# LinuxBoard_v1_7.net
KiCad netlist of a schematic drawn in EAGLE
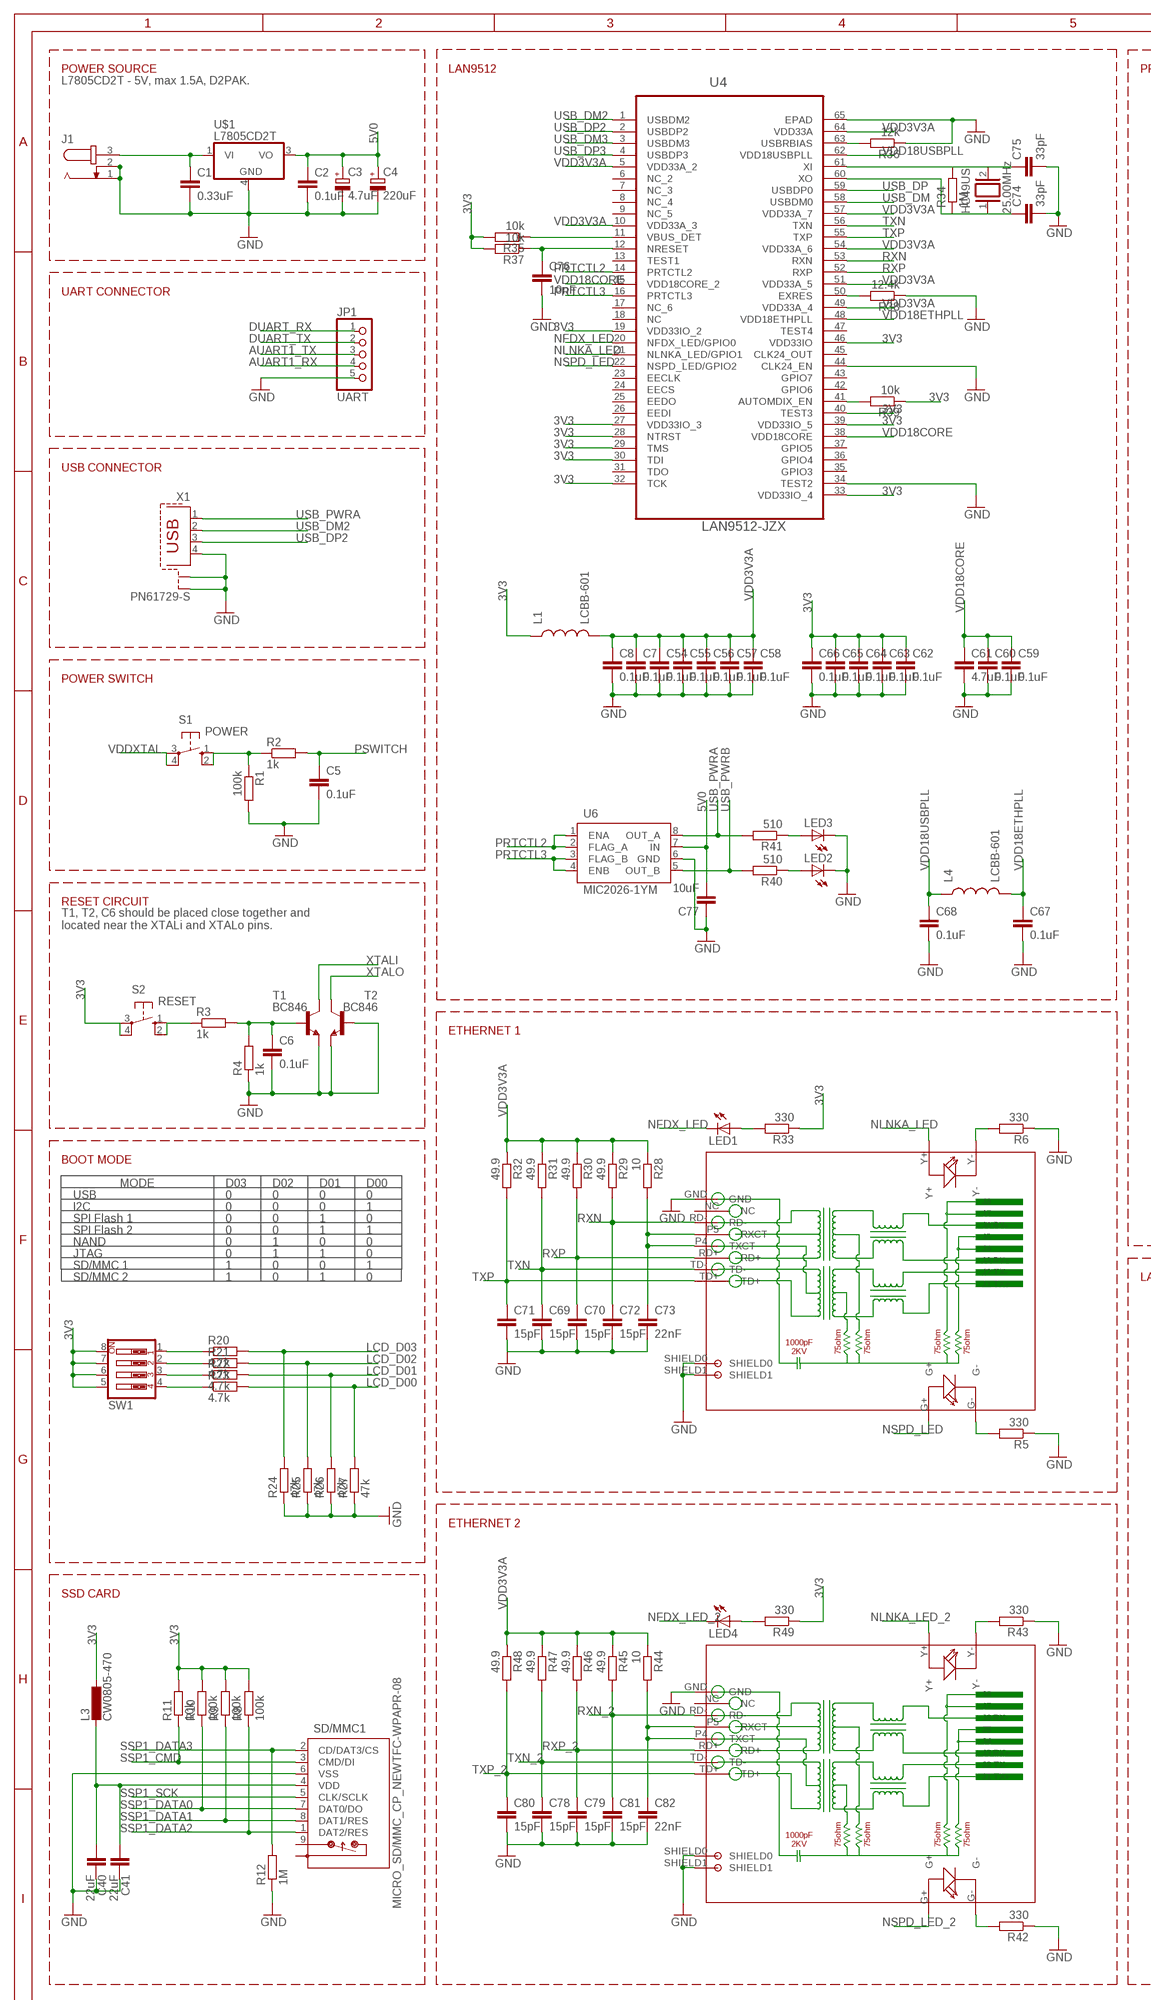
[diagram p0: schematic, sheet 1, part 1 of 2]
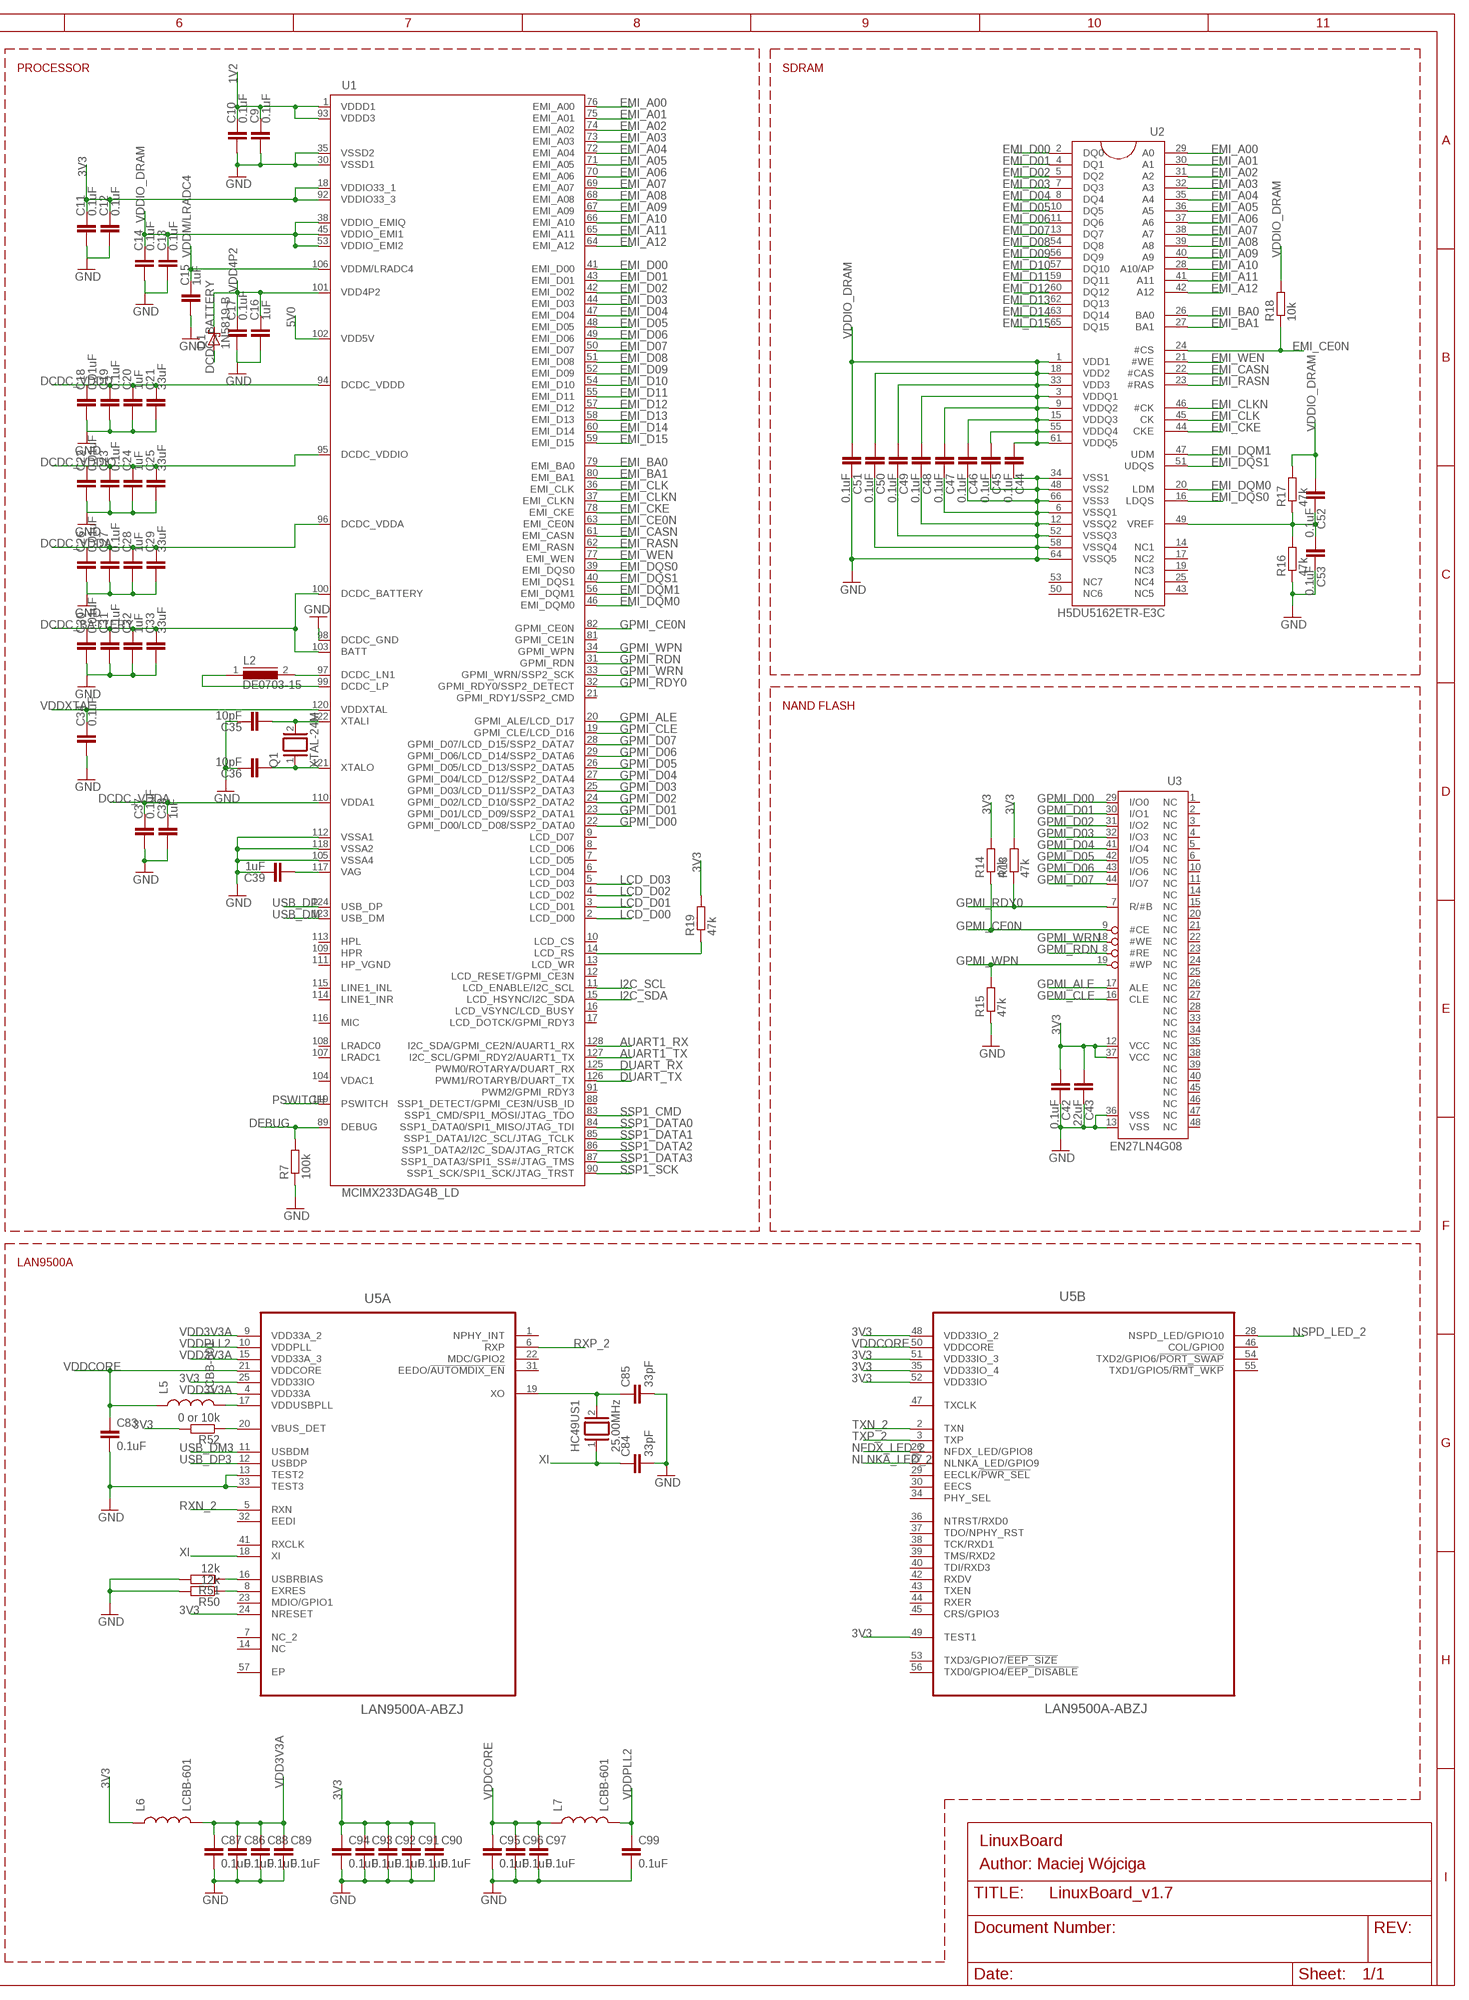
[diagram p1: schematic, sheet 1, part 2 of 2]

(export (version "E")
  (design (tool "Eeschema 10.0.6"))
  (components
    (comp (ref "C1")
      (value "0.33uF")
      (footprint "eagle-import:C0805")
      (libsource (lib "eagle-import") (part "C-EUC0805"))
    )
    (comp (ref "C2")
      (value "0.1uF")
      (footprint "eagle-import:C0805")
      (libsource (lib "eagle-import") (part "C-EUC0805"))
    )
    (comp (ref "C3")
      (value "4.7uF")
      (footprint "eagle-import:E2-5")
      (libsource (lib "eagle-import") (part "CPOL-EUE2-5"))
    )
    (comp (ref "C4")
      (value "220uF")
      (footprint "eagle-import:E2-5")
      (libsource (lib "eagle-import") (part "CPOL-EUE2-5"))
    )
    (comp (ref "C5")
      (value "0.1uF")
      (footprint "eagle-import:C0805")
      (libsource (lib "eagle-import") (part "C-EUC0805"))
    )
    (comp (ref "C6")
      (value "0.1uF")
      (footprint "eagle-import:C0805")
      (libsource (lib "eagle-import") (part "C-EUC0805"))
    )
    (comp (ref "C7")
      (value "0.1uF")
      (footprint "eagle-import:C0805")
      (libsource (lib "eagle-import") (part "C-EUC0805"))
    )
    (comp (ref "C8")
      (value "0.1uF")
      (footprint "eagle-import:C0805")
      (libsource (lib "eagle-import") (part "C-EUC0805"))
    )
    (comp (ref "C9")
      (value "0.1uF")
      (footprint "eagle-import:C0805")
      (libsource (lib "eagle-import") (part "C-EUC0805"))
    )
    (comp (ref "C10")
      (value "0.1uF")
      (footprint "eagle-import:C0805")
      (libsource (lib "eagle-import") (part "C-EUC0805"))
    )
    (comp (ref "C11")
      (value "0.1uF")
      (footprint "eagle-import:C0805")
      (libsource (lib "eagle-import") (part "C-EUC0805"))
    )
    (comp (ref "C12")
      (value "0.1uF")
      (footprint "eagle-import:C0805")
      (libsource (lib "eagle-import") (part "C-EUC0805"))
    )
    (comp (ref "C13")
      (value "0.1uF")
      (footprint "eagle-import:C0805")
      (libsource (lib "eagle-import") (part "C-EUC0805"))
    )
    (comp (ref "C14")
      (value "0.1uF")
      (footprint "eagle-import:C0805")
      (libsource (lib "eagle-import") (part "C-EUC0805"))
    )
    (comp (ref "C15")
      (value "1uF")
      (footprint "eagle-import:C0805")
      (libsource (lib "eagle-import") (part "C-EUC0805"))
    )
    (comp (ref "C16")
      (value "1uF")
      (footprint "eagle-import:C0805")
      (libsource (lib "eagle-import") (part "C-EUC0805"))
    )
    (comp (ref "C17")
      (value "0.1uF")
      (footprint "eagle-import:C0805")
      (libsource (lib "eagle-import") (part "C-EUC0805"))
    )
    (comp (ref "C18")
      (value "0.01uF")
      (footprint "eagle-import:C0805")
      (libsource (lib "eagle-import") (part "C-EUC0805"))
    )
    (comp (ref "C19")
      (value "0.1uF")
      (footprint "eagle-import:C0805")
      (libsource (lib "eagle-import") (part "C-EUC0805"))
    )
    (comp (ref "C20")
      (value "1uF")
      (footprint "eagle-import:C0805")
      (libsource (lib "eagle-import") (part "C-EUC0805"))
    )
    (comp (ref "C21")
      (value "33uF")
      (footprint "eagle-import:C0805")
      (libsource (lib "eagle-import") (part "C-EUC0805"))
    )
    (comp (ref "C22")
      (value "0.01uF")
      (footprint "eagle-import:C0805")
      (libsource (lib "eagle-import") (part "C-EUC0805"))
    )
    (comp (ref "C23")
      (value "0.1uF")
      (footprint "eagle-import:C0805")
      (libsource (lib "eagle-import") (part "C-EUC0805"))
    )
    (comp (ref "C24")
      (value "1uF")
      (footprint "eagle-import:C0805")
      (libsource (lib "eagle-import") (part "C-EUC0805"))
    )
    (comp (ref "C25")
      (value "33uF")
      (footprint "eagle-import:C0805")
      (libsource (lib "eagle-import") (part "C-EUC0805"))
    )
    (comp (ref "C26")
      (value "0.01uF")
      (footprint "eagle-import:C0805")
      (libsource (lib "eagle-import") (part "C-EUC0805"))
    )
    (comp (ref "C27")
      (value "0.1uF")
      (footprint "eagle-import:C0805")
      (libsource (lib "eagle-import") (part "C-EUC0805"))
    )
    (comp (ref "C28")
      (value "1uF")
      (footprint "eagle-import:C0805")
      (libsource (lib "eagle-import") (part "C-EUC0805"))
    )
    (comp (ref "C29")
      (value "33uF")
      (footprint "eagle-import:C0805")
      (libsource (lib "eagle-import") (part "C-EUC0805"))
    )
    (comp (ref "C30")
      (value "0.01uF")
      (footprint "eagle-import:C0805")
      (libsource (lib "eagle-import") (part "C-EUC0805"))
    )
    (comp (ref "C31")
      (value "0.1uF")
      (footprint "eagle-import:C0805")
      (libsource (lib "eagle-import") (part "C-EUC0805"))
    )
    (comp (ref "C32")
      (value "1uF")
      (footprint "eagle-import:C0805")
      (libsource (lib "eagle-import") (part "C-EUC0805"))
    )
    (comp (ref "C33")
      (value "33uF")
      (footprint "eagle-import:C0805")
      (libsource (lib "eagle-import") (part "C-EUC0805"))
    )
    (comp (ref "C34")
      (value "0.1uF")
      (footprint "eagle-import:C0805")
      (libsource (lib "eagle-import") (part "C-EUC0805"))
    )
    (comp (ref "C35")
      (value "10pF")
      (footprint "eagle-import:C0805")
      (libsource (lib "eagle-import") (part "C-EUC0805"))
    )
    (comp (ref "C36")
      (value "10pF")
      (footprint "eagle-import:C0805")
      (libsource (lib "eagle-import") (part "C-EUC0805"))
    )
    (comp (ref "C37")
      (value "0.1uF")
      (footprint "eagle-import:C0805")
      (libsource (lib "eagle-import") (part "C-EUC0805"))
    )
    (comp (ref "C38")
      (value "1uF")
      (footprint "eagle-import:C0805")
      (libsource (lib "eagle-import") (part "C-EUC0805"))
    )
    (comp (ref "C39")
      (value "1uF")
      (footprint "eagle-import:C0805")
      (libsource (lib "eagle-import") (part "C-EUC0805"))
    )
    (comp (ref "C40")
      (value "22uF")
      (footprint "eagle-import:C0805")
      (libsource (lib "eagle-import") (part "C-EUC0805"))
    )
    (comp (ref "C41")
      (value "22uF")
      (footprint "eagle-import:C0805")
      (libsource (lib "eagle-import") (part "C-EUC0805"))
    )
    (comp (ref "C42")
      (value "0.1uF")
      (footprint "eagle-import:C0805")
      (libsource (lib "eagle-import") (part "C-EUC0805"))
    )
    (comp (ref "C43")
      (value "22uF")
      (footprint "eagle-import:C0805")
      (libsource (lib "eagle-import") (part "C-EUC0805"))
    )
    (comp (ref "C44")
      (value "0.1uF")
      (footprint "eagle-import:C0805")
      (libsource (lib "eagle-import") (part "C-EUC0805"))
    )
    (comp (ref "C45")
      (value "0.1uF")
      (footprint "eagle-import:C0805")
      (libsource (lib "eagle-import") (part "C-EUC0805"))
    )
    (comp (ref "C46")
      (value "0.1uF")
      (footprint "eagle-import:C0805")
      (libsource (lib "eagle-import") (part "C-EUC0805"))
    )
    (comp (ref "C47")
      (value "0.1uF")
      (footprint "eagle-import:C0805")
      (libsource (lib "eagle-import") (part "C-EUC0805"))
    )
    (comp (ref "C48")
      (value "0.1uF")
      (footprint "eagle-import:C0805")
      (libsource (lib "eagle-import") (part "C-EUC0805"))
    )
    (comp (ref "C49")
      (value "0.1uF")
      (footprint "eagle-import:C0805")
      (libsource (lib "eagle-import") (part "C-EUC0805"))
    )
    (comp (ref "C50")
      (value "0.1uF")
      (footprint "eagle-import:C0805")
      (libsource (lib "eagle-import") (part "C-EUC0805"))
    )
    (comp (ref "C51")
      (value "0.1uF")
      (footprint "eagle-import:C0805")
      (libsource (lib "eagle-import") (part "C-EUC0805"))
    )
    (comp (ref "C52")
      (value "0.1uF")
      (footprint "eagle-import:C0805")
      (libsource (lib "eagle-import") (part "C-EUC0805"))
    )
    (comp (ref "C53")
      (value "0.1uF")
      (footprint "eagle-import:C0805")
      (libsource (lib "eagle-import") (part "C-EUC0805"))
    )
    (comp (ref "C54")
      (value "0.1uF")
      (footprint "eagle-import:C0805")
      (libsource (lib "eagle-import") (part "C-EUC0805"))
    )
    (comp (ref "C55")
      (value "0.1uF")
      (footprint "eagle-import:C0805")
      (libsource (lib "eagle-import") (part "C-EUC0805"))
    )
    (comp (ref "C56")
      (value "0.1uF")
      (footprint "eagle-import:C0805")
      (libsource (lib "eagle-import") (part "C-EUC0805"))
    )
    (comp (ref "C57")
      (value "0.1uF")
      (footprint "eagle-import:C0805")
      (libsource (lib "eagle-import") (part "C-EUC0805"))
    )
    (comp (ref "C58")
      (value "0.1uF")
      (footprint "eagle-import:C0805")
      (libsource (lib "eagle-import") (part "C-EUC0805"))
    )
    (comp (ref "C59")
      (value "0.1uF")
      (footprint "eagle-import:C0805")
      (libsource (lib "eagle-import") (part "C-EUC0805"))
    )
    (comp (ref "C60")
      (value "0.1uF")
      (footprint "eagle-import:C0805")
      (libsource (lib "eagle-import") (part "C-EUC0805"))
    )
    (comp (ref "C61")
      (value "4.7uF")
      (footprint "eagle-import:C0805")
      (libsource (lib "eagle-import") (part "C-EUC0805"))
    )
    (comp (ref "C62")
      (value "0.1uF")
      (footprint "eagle-import:C0805")
      (libsource (lib "eagle-import") (part "C-EUC0805"))
    )
    (comp (ref "C63")
      (value "0.1uF")
      (footprint "eagle-import:C0805")
      (libsource (lib "eagle-import") (part "C-EUC0805"))
    )
    (comp (ref "C64")
      (value "0.1uF")
      (footprint "eagle-import:C0805")
      (libsource (lib "eagle-import") (part "C-EUC0805"))
    )
    (comp (ref "C65")
      (value "0.1uF")
      (footprint "eagle-import:C0805")
      (libsource (lib "eagle-import") (part "C-EUC0805"))
    )
    (comp (ref "C66")
      (value "0.1uF")
      (footprint "eagle-import:C0805")
      (libsource (lib "eagle-import") (part "C-EUC0805"))
    )
    (comp (ref "C67")
      (value "0.1uF")
      (footprint "eagle-import:C0805")
      (libsource (lib "eagle-import") (part "C-EUC0805"))
    )
    (comp (ref "C68")
      (value "0.1uF")
      (footprint "eagle-import:C0805")
      (libsource (lib "eagle-import") (part "C-EUC0805"))
    )
    (comp (ref "C69")
      (value "15pF")
      (footprint "eagle-import:C0805")
      (libsource (lib "eagle-import") (part "C-EUC0805"))
    )
    (comp (ref "C70")
      (value "15pF")
      (footprint "eagle-import:C0805")
      (libsource (lib "eagle-import") (part "C-EUC0805"))
    )
    (comp (ref "C71")
      (value "15pF")
      (footprint "eagle-import:C0805")
      (libsource (lib "eagle-import") (part "C-EUC0805"))
    )
    (comp (ref "C72")
      (value "15pF")
      (footprint "eagle-import:C0805")
      (libsource (lib "eagle-import") (part "C-EUC0805"))
    )
    (comp (ref "C73")
      (value "22nF")
      (footprint "eagle-import:C0805")
      (libsource (lib "eagle-import") (part "C-EUC0805"))
    )
    (comp (ref "C74")
      (value "33pF")
      (footprint "eagle-import:C0805")
      (libsource (lib "eagle-import") (part "C-EUC0805"))
    )
    (comp (ref "C75")
      (value "33pF")
      (footprint "eagle-import:C0805")
      (libsource (lib "eagle-import") (part "C-EUC0805"))
    )
    (comp (ref "C76")
      (value "10nF")
      (footprint "eagle-import:C0805")
      (libsource (lib "eagle-import") (part "C-EUC0805"))
    )
    (comp (ref "C77")
      (value "10uF")
      (footprint "eagle-import:C0805")
      (libsource (lib "eagle-import") (part "C-EUC0805"))
    )
    (comp (ref "C78")
      (value "15pF")
      (footprint "eagle-import:C0805")
      (libsource (lib "eagle-import") (part "C-EUC0805"))
    )
    (comp (ref "C79")
      (value "15pF")
      (footprint "eagle-import:C0805")
      (libsource (lib "eagle-import") (part "C-EUC0805"))
    )
    (comp (ref "C80")
      (value "15pF")
      (footprint "eagle-import:C0805")
      (libsource (lib "eagle-import") (part "C-EUC0805"))
    )
    (comp (ref "C81")
      (value "15pF")
      (footprint "eagle-import:C0805")
      (libsource (lib "eagle-import") (part "C-EUC0805"))
    )
    (comp (ref "C82")
      (value "22nF")
      (footprint "eagle-import:C0805")
      (libsource (lib "eagle-import") (part "C-EUC0805"))
    )
    (comp (ref "C83")
      (value "0.1uF")
      (footprint "eagle-import:C0805")
      (libsource (lib "eagle-import") (part "C-EUC0805"))
    )
    (comp (ref "C84")
      (value "33pF")
      (footprint "eagle-import:C0805")
      (libsource (lib "eagle-import") (part "C-EUC0805"))
    )
    (comp (ref "C85")
      (value "33pF")
      (footprint "eagle-import:C0805")
      (libsource (lib "eagle-import") (part "C-EUC0805"))
    )
    (comp (ref "C86")
      (value "0.1uF")
      (footprint "eagle-import:C0805")
      (libsource (lib "eagle-import") (part "C-EUC0805"))
    )
    (comp (ref "C87")
      (value "0.1uF")
      (footprint "eagle-import:C0805")
      (libsource (lib "eagle-import") (part "C-EUC0805"))
    )
    (comp (ref "C88")
      (value "0.1uF")
      (footprint "eagle-import:C0805")
      (libsource (lib "eagle-import") (part "C-EUC0805"))
    )
    (comp (ref "C89")
      (value "0.1uF")
      (footprint "eagle-import:C0805")
      (libsource (lib "eagle-import") (part "C-EUC0805"))
    )
    (comp (ref "C90")
      (value "0.1uF")
      (footprint "eagle-import:C0805")
      (libsource (lib "eagle-import") (part "C-EUC0805"))
    )
    (comp (ref "C91")
      (value "0.1uF")
      (footprint "eagle-import:C0805")
      (libsource (lib "eagle-import") (part "C-EUC0805"))
    )
    (comp (ref "C92")
      (value "0.1uF")
      (footprint "eagle-import:C0805")
      (libsource (lib "eagle-import") (part "C-EUC0805"))
    )
    (comp (ref "C93")
      (value "0.1uF")
      (footprint "eagle-import:C0805")
      (libsource (lib "eagle-import") (part "C-EUC0805"))
    )
    (comp (ref "C94")
      (value "0.1uF")
      (footprint "eagle-import:C0805")
      (libsource (lib "eagle-import") (part "C-EUC0805"))
    )
    (comp (ref "C95")
      (value "0.1uF")
      (footprint "eagle-import:C0805")
      (libsource (lib "eagle-import") (part "C-EUC0805"))
    )
    (comp (ref "C96")
      (value "0.1uF")
      (footprint "eagle-import:C0805")
      (libsource (lib "eagle-import") (part "C-EUC0805"))
    )
    (comp (ref "C97")
      (value "0.1uF")
      (footprint "eagle-import:C0805")
      (libsource (lib "eagle-import") (part "C-EUC0805"))
    )
    (comp (ref "C99")
      (value "0.1uF")
      (footprint "eagle-import:C0805")
      (libsource (lib "eagle-import") (part "C-EUC0805"))
    )
    (comp (ref "D1")
      (value "1N5819-B")
      (footprint "eagle-import:DO41-7.6")
      (libsource (lib "eagle-import") (part "1N5819-B"))
    )
    (comp (ref "HC49US")
      (value "25.00MHz")
      (footprint "eagle-import:QS")
      (libsource (lib "eagle-import") (part "XTAL/S"))
    )
    (comp (ref "HC49US1")
      (value "25.00MHz")
      (footprint "eagle-import:QS")
      (libsource (lib "eagle-import") (part "XTAL/S"))
    )
    (comp (ref "J1")
      (value "JACK-PLUG0")
      (footprint "eagle-import:SPC4077")
      (libsource (lib "eagle-import") (part "JACK-PLUG0"))
    )
    (comp (ref "JP1")
      (value "UART")
      (footprint "eagle-import:1X05")
      (libsource (lib "eagle-import") (part "PINHD-1X5"))
    )
    (comp (ref "L1")
      (value "LCBB-601")
      (footprint "eagle-import:0805")
      (libsource (lib "eagle-import") (part "INDUCTOR0805"))
    )
    (comp (ref "L2")
      (value "DE0703-15")
      (footprint "eagle-import:DR73")
      (libsource (lib "eagle-import") (part "DR73"))
    )
    (comp (ref "L3")
      (value "CW0805-470")
      (footprint "eagle-import:L2012C")
      (libsource (lib "eagle-import") (part "L-EUL2012C"))
    )
    (comp (ref "L4")
      (value "LCBB-601")
      (footprint "eagle-import:0805")
      (libsource (lib "eagle-import") (part "INDUCTOR0805"))
    )
    (comp (ref "L5")
      (value "LCBB-601")
      (footprint "eagle-import:0805")
      (libsource (lib "eagle-import") (part "INDUCTOR0805"))
    )
    (comp (ref "L6")
      (value "LCBB-601")
      (footprint "eagle-import:0805")
      (libsource (lib "eagle-import") (part "INDUCTOR0805"))
    )
    (comp (ref "L7")
      (value "LCBB-601")
      (footprint "eagle-import:0805")
      (libsource (lib "eagle-import") (part "INDUCTOR0805"))
    )
    (comp (ref "LED1")
      (value "LEDSML0805")
      (footprint "eagle-import:SML0805")
      (libsource (lib "eagle-import") (part "LEDSML0805"))
    )
    (comp (ref "LED2")
      (value "LEDSML0805")
      (footprint "eagle-import:SML0805")
      (libsource (lib "eagle-import") (part "LEDSML0805"))
    )
    (comp (ref "LED3")
      (value "LEDSML0805")
      (footprint "eagle-import:SML0805")
      (libsource (lib "eagle-import") (part "LEDSML0805"))
    )
    (comp (ref "LED4")
      (value "LEDSML0805")
      (footprint "eagle-import:SML0805")
      (libsource (lib "eagle-import") (part "LEDSML0805"))
    )
    (comp (ref "Q1")
      (value "XTAL-24M")
      (footprint "eagle-import:QS")
      (libsource (lib "eagle-import") (part "XTAL/S"))
    )
    (comp (ref "R1")
      (value "100k")
      (footprint "eagle-import:R0805")
      (libsource (lib "eagle-import") (part "R-EU_R0805"))
    )
    (comp (ref "R2")
      (value "1k")
      (footprint "eagle-import:R0805")
      (libsource (lib "eagle-import") (part "R-EU_R0805"))
    )
    (comp (ref "R3")
      (value "1k")
      (footprint "eagle-import:R0805")
      (libsource (lib "eagle-import") (part "R-EU_R0805"))
    )
    (comp (ref "R4")
      (value "1k")
      (footprint "eagle-import:R0805")
      (libsource (lib "eagle-import") (part "R-EU_R0805"))
    )
    (comp (ref "R5")
      (value "330")
      (footprint "eagle-import:R0805")
      (libsource (lib "eagle-import") (part "R-EU_R0805"))
    )
    (comp (ref "R6")
      (value "330")
      (footprint "eagle-import:R0805")
      (libsource (lib "eagle-import") (part "R-EU_R0805"))
    )
    (comp (ref "R7")
      (value "100k")
      (footprint "eagle-import:R0805")
      (libsource (lib "eagle-import") (part "R-EU_R0805"))
    )
    (comp (ref "R8")
      (value "100k")
      (footprint "eagle-import:R0805")
      (libsource (lib "eagle-import") (part "R-EU_R0805"))
    )
    (comp (ref "R9")
      (value "100k")
      (footprint "eagle-import:R0805")
      (libsource (lib "eagle-import") (part "R-EU_R0805"))
    )
    (comp (ref "R10")
      (value "100k")
      (footprint "eagle-import:R0805")
      (libsource (lib "eagle-import") (part "R-EU_R0805"))
    )
    (comp (ref "R11")
      (value "10k")
      (footprint "eagle-import:R0805")
      (libsource (lib "eagle-import") (part "R-EU_R0805"))
    )
    (comp (ref "R12")
      (value "1M")
      (footprint "eagle-import:R0805")
      (libsource (lib "eagle-import") (part "R-EU_R0805"))
    )
    (comp (ref "R13")
      (value "47k")
      (footprint "eagle-import:R0805")
      (libsource (lib "eagle-import") (part "R-EU_R0805"))
    )
    (comp (ref "R14")
      (value "47k")
      (footprint "eagle-import:R0805")
      (libsource (lib "eagle-import") (part "R-EU_R0805"))
    )
    (comp (ref "R15")
      (value "47k")
      (footprint "eagle-import:R0805")
      (libsource (lib "eagle-import") (part "R-EU_R0805"))
    )
    (comp (ref "R16")
      (value "47k")
      (footprint "eagle-import:R0805")
      (libsource (lib "eagle-import") (part "R-EU_R0805"))
    )
    (comp (ref "R17")
      (value "47k")
      (footprint "eagle-import:R0805")
      (libsource (lib "eagle-import") (part "R-EU_R0805"))
    )
    (comp (ref "R18")
      (value "10k")
      (footprint "eagle-import:R0805")
      (libsource (lib "eagle-import") (part "R-EU_R0805"))
    )
    (comp (ref "R19")
      (value "47k")
      (footprint "eagle-import:R0805")
      (libsource (lib "eagle-import") (part "R-EU_R0805"))
    )
    (comp (ref "R20")
      (value "4.7k")
      (footprint "eagle-import:R0805")
      (libsource (lib "eagle-import") (part "R-EU_R0805"))
    )
    (comp (ref "R21")
      (value "4.7k")
      (footprint "eagle-import:R0805")
      (libsource (lib "eagle-import") (part "R-EU_R0805"))
    )
    (comp (ref "R22")
      (value "4.7k")
      (footprint "eagle-import:R0805")
      (libsource (lib "eagle-import") (part "R-EU_R0805"))
    )
    (comp (ref "R23")
      (value "4.7k")
      (footprint "eagle-import:R0805")
      (libsource (lib "eagle-import") (part "R-EU_R0805"))
    )
    (comp (ref "R24")
      (value "47k")
      (footprint "eagle-import:R0805")
      (libsource (lib "eagle-import") (part "R-EU_R0805"))
    )
    (comp (ref "R25")
      (value "47k")
      (footprint "eagle-import:R0805")
      (libsource (lib "eagle-import") (part "R-EU_R0805"))
    )
    (comp (ref "R26")
      (value "47k")
      (footprint "eagle-import:R0805")
      (libsource (lib "eagle-import") (part "R-EU_R0805"))
    )
    (comp (ref "R27")
      (value "47k")
      (footprint "eagle-import:R0805")
      (libsource (lib "eagle-import") (part "R-EU_R0805"))
    )
    (comp (ref "R28")
      (value "10")
      (footprint "eagle-import:R0805")
      (libsource (lib "eagle-import") (part "R-EU_R0805"))
    )
    (comp (ref "R29")
      (value "49.9")
      (footprint "eagle-import:R0805")
      (libsource (lib "eagle-import") (part "R-EU_R0805"))
    )
    (comp (ref "R30")
      (value "49.9")
      (footprint "eagle-import:R0805")
      (libsource (lib "eagle-import") (part "R-EU_R0805"))
    )
    (comp (ref "R31")
      (value "49.9")
      (footprint "eagle-import:R0805")
      (libsource (lib "eagle-import") (part "R-EU_R0805"))
    )
    (comp (ref "R32")
      (value "49.9")
      (footprint "eagle-import:R0805")
      (libsource (lib "eagle-import") (part "R-EU_R0805"))
    )
    (comp (ref "R33")
      (value "330")
      (footprint "eagle-import:R0805")
      (libsource (lib "eagle-import") (part "R-EU_R0805"))
    )
    (comp (ref "R34")
      (value "1M")
      (footprint "eagle-import:R0805")
      (libsource (lib "eagle-import") (part "R-EU_R0805"))
    )
    (comp (ref "R35")
      (value "10k")
      (footprint "eagle-import:R0805")
      (libsource (lib "eagle-import") (part "R-EU_R0805"))
    )
    (comp (ref "R36")
      (value "12k")
      (footprint "eagle-import:R0805")
      (libsource (lib "eagle-import") (part "R-EU_R0805"))
    )
    (comp (ref "R37")
      (value "10k")
      (footprint "eagle-import:R0805")
      (libsource (lib "eagle-import") (part "R-EU_R0805"))
    )
    (comp (ref "R38")
      (value "12.4k")
      (footprint "eagle-import:R0805")
      (libsource (lib "eagle-import") (part "R-EU_R0805"))
    )
    (comp (ref "R39")
      (value "10k")
      (footprint "eagle-import:R0805")
      (libsource (lib "eagle-import") (part "R-EU_R0805"))
    )
    (comp (ref "R40")
      (value "510")
      (footprint "eagle-import:R0805")
      (libsource (lib "eagle-import") (part "R-EU_R0805"))
    )
    (comp (ref "R41")
      (value "510")
      (footprint "eagle-import:R0805")
      (libsource (lib "eagle-import") (part "R-EU_R0805"))
    )
    (comp (ref "R42")
      (value "330")
      (footprint "eagle-import:R0805")
      (libsource (lib "eagle-import") (part "R-EU_R0805"))
    )
    (comp (ref "R43")
      (value "330")
      (footprint "eagle-import:R0805")
      (libsource (lib "eagle-import") (part "R-EU_R0805"))
    )
    (comp (ref "R44")
      (value "10")
      (footprint "eagle-import:R0805")
      (libsource (lib "eagle-import") (part "R-EU_R0805"))
    )
    (comp (ref "R45")
      (value "49.9")
      (footprint "eagle-import:R0805")
      (libsource (lib "eagle-import") (part "R-EU_R0805"))
    )
    (comp (ref "R46")
      (value "49.9")
      (footprint "eagle-import:R0805")
      (libsource (lib "eagle-import") (part "R-EU_R0805"))
    )
    (comp (ref "R47")
      (value "49.9")
      (footprint "eagle-import:R0805")
      (libsource (lib "eagle-import") (part "R-EU_R0805"))
    )
    (comp (ref "R48")
      (value "49.9")
      (footprint "eagle-import:R0805")
      (libsource (lib "eagle-import") (part "R-EU_R0805"))
    )
    (comp (ref "R49")
      (value "330")
      (footprint "eagle-import:R0805")
      (libsource (lib "eagle-import") (part "R-EU_R0805"))
    )
    (comp (ref "R50")
      (value "12k")
      (footprint "eagle-import:R0805")
      (libsource (lib "eagle-import") (part "R-EU_R0805"))
    )
    (comp (ref "R51")
      (value "12k")
      (footprint "eagle-import:R0805")
      (libsource (lib "eagle-import") (part "R-EU_R0805"))
    )
    (comp (ref "R52")
      (value "0 or 10k")
      (footprint "eagle-import:R0805")
      (libsource (lib "eagle-import") (part "R-EU_R0805"))
    )
    (comp (ref "RJ1")
      (value "HR911105A")
      (footprint "eagle-import:HR911105A")
      (libsource (lib "eagle-import") (part "HR911105A"))
    )
    (comp (ref "RJ2")
      (value "HR911105A")
      (footprint "eagle-import:HR911105A")
      (libsource (lib "eagle-import") (part "HR911105A"))
    )
    (comp (ref "S1")
      (value "POWER")
      (footprint "eagle-import:B3F-10XX")
      (fields (field (name "MPN") "B3F-1000"))
      (libsource (lib "eagle-import") (part "10-XX"))
    )
    (comp (ref "S2")
      (value "RESET")
      (footprint "eagle-import:B3F-10XX")
      (fields (field (name "MPN") "B3F-1000"))
      (libsource (lib "eagle-import") (part "10-XX"))
    )
    (comp (ref "SD/MMC1")
      (value "MICRO_SD/MMC_CP_NEWTFC-WPAPR-08")
      (footprint "eagle-import:TFC-WPAPR-08")
      (libsource (lib "eagle-import") (part "MICRO_SD/MMC_CP_NEWTFC-WPAPR-08"))
    )
    (comp (ref "SW1")
      (value "SW_DIP-4")
      (footprint "eagle-import:EDG-04")
      (libsource (lib "eagle-import") (part "SW_DIP-4"))
    )
    (comp (ref "T1")
      (value "BC846")
      (footprint "eagle-import:SOT23")
      (libsource (lib "eagle-import") (part "BC846"))
    )
    (comp (ref "T2")
      (value "BC846")
      (footprint "eagle-import:SOT23")
      (libsource (lib "eagle-import") (part "BC846"))
    )
    (comp (ref "U$1")
      (value "L7805CD2T")
      (footprint "eagle-import:D2PAK-3")
      (libsource (lib "eagle-import") (part "L7805CD2T"))
    )
    (comp (ref "U1")
      (value "MCIMX233DAG4B_LD")
      (footprint "eagle-import:TQFP128LD")
      (libsource (lib "eagle-import") (part "MCIMX233DAG4B_LD"))
    )
    (comp (ref "U2")
      (value "H5DU5162ETR-E3C")
      (footprint "eagle-import:66TSOP-II")
      (libsource (lib "eagle-import") (part "HY5DU121622D(L)T(P)-J"))
    )
    (comp (ref "U3")
      (value "EN27LN4G08")
      (footprint "eagle-import:TSOP48")
      (libsource (lib "eagle-import") (part "H27UBG8T2A"))
    )
    (comp (ref "U4")
      (value "LAN9512-JZX")
      (footprint "eagle-import:QFN50P900X900X100-65N")
      (libsource (lib "eagle-import") (part "LAN9512-JZX"))
    )
    (comp (ref "U5")
      (value "LAN9500A-ABZJ")
      (footprint "eagle-import:QFN50P800X800X100-57N")
      (libsource (lib "eagle-import") (part "LAN9500A-ABZJ"))
    )
    (comp (ref "U6")
      (value "MIC2026-1YM")
      (footprint "eagle-import:SO-8")
      (libsource (lib "eagle-import") (part "MIC2026-1YM"))
    )
    (comp (ref "X1")
      (value "PN61729-S")
      (footprint "eagle-import:PN61729-S")
      (libsource (lib "eagle-import") (part "PN61729-S"))
    )
  )
  (nets
    (net (code "1") (name "/1V2") (class "Default")
      (node (ref "C10") (pin "1") (pinfunction "1_1") (pintype "passive"))
      (node (ref "C9") (pin "1") (pinfunction "1_1") (pintype "passive"))
      (node (ref "U1") (pin "1") (pinfunction "VDDD1_1") (pintype "power_in"))
      (node (ref "U1") (pin "93") (pinfunction "VDDD3_93") (pintype "power_in"))
    )
    (net (code "2") (name "/3V3") (class "Default")
      (node (ref "C11") (pin "1") (pinfunction "1_1") (pintype "passive"))
      (node (ref "C12") (pin "1") (pinfunction "1_1") (pintype "passive"))
      (node (ref "C42") (pin "2") (pinfunction "2_2") (pintype "passive"))
      (node (ref "C43") (pin "2") (pinfunction "2_2") (pintype "passive"))
      (node (ref "C62") (pin "1") (pinfunction "1_1") (pintype "passive"))
      (node (ref "C63") (pin "1") (pinfunction "1_1") (pintype "passive"))
      (node (ref "C64") (pin "1") (pinfunction "1_1") (pintype "passive"))
      (node (ref "C65") (pin "1") (pinfunction "1_1") (pintype "passive"))
      (node (ref "C66") (pin "1") (pinfunction "1_1") (pintype "passive"))
      (node (ref "C90") (pin "1") (pinfunction "1_1") (pintype "passive"))
      (node (ref "C91") (pin "1") (pinfunction "1_1") (pintype "passive"))
      (node (ref "C92") (pin "1") (pinfunction "1_1") (pintype "passive"))
      (node (ref "C93") (pin "1") (pinfunction "1_1") (pintype "passive"))
      (node (ref "C94") (pin "1") (pinfunction "1_1") (pintype "passive"))
      (node (ref "L1") (pin "1") (pinfunction "1_1") (pintype "passive"))
      (node (ref "L3") (pin "1") (pinfunction "1_1") (pintype "passive"))
      (node (ref "L6") (pin "1") (pinfunction "1_1") (pintype "passive"))
      (node (ref "R10") (pin "2") (pinfunction "2_2") (pintype "passive"))
      (node (ref "R11") (pin "2") (pinfunction "2_2") (pintype "passive"))
      (node (ref "R13") (pin "2") (pinfunction "2_2") (pintype "passive"))
      (node (ref "R14") (pin "2") (pinfunction "2_2") (pintype "passive"))
      (node (ref "R19") (pin "2") (pinfunction "2_2") (pintype "passive"))
      (node (ref "R33") (pin "1") (pinfunction "1_1") (pintype "passive"))
      (node (ref "R35") (pin "2") (pinfunction "2_2") (pintype "passive"))
      (node (ref "R37") (pin "2") (pinfunction "2_2") (pintype "passive"))
      (node (ref "R39") (pin "1") (pinfunction "1_1") (pintype "passive"))
      (node (ref "R49") (pin "1") (pinfunction "1_1") (pintype "passive"))
      (node (ref "R52") (pin "2") (pinfunction "2_2") (pintype "passive"))
      (node (ref "R8") (pin "2") (pinfunction "2_2") (pintype "passive"))
      (node (ref "R9") (pin "2") (pinfunction "2_2") (pintype "passive"))
      (node (ref "S2") (pin "3") (pinfunction "P_3") (pintype "passive"))
      (node (ref "S2") (pin "4") (pinfunction "P1_4") (pintype "passive"))
      (node (ref "SW1") (pin "5") (pinfunction "5_5") (pintype "passive"))
      (node (ref "SW1") (pin "6") (pinfunction "6_6") (pintype "passive"))
      (node (ref "SW1") (pin "7") (pinfunction "7_7") (pintype "passive"))
      (node (ref "SW1") (pin "8") (pinfunction "8_8") (pintype "passive"))
      (node (ref "U1") (pin "18") (pinfunction "VDDIO33_1_18") (pintype "power_in"))
      (node (ref "U1") (pin "92") (pinfunction "VDDIO33_3_92") (pintype "power_in"))
      (node (ref "U3") (pin "12") (pinfunction "VCC_12") (pintype "power_in"))
      (node (ref "U3") (pin "37") (pinfunction "VCC_37") (pintype "power_in"))
      (node (ref "U4") (pin "19") (pinfunction "VDD33IO_2_19") (pintype "power_in"))
      (node (ref "U4") (pin "27") (pinfunction "VDD33IO_3_27") (pintype "power_in"))
      (node (ref "U4") (pin "28") (pinfunction "NTRST_28") (pintype "passive"))
      (node (ref "U4") (pin "29") (pinfunction "TMS_29") (pintype "passive"))
      (node (ref "U4") (pin "30") (pinfunction "TDI_30") (pintype "passive"))
      (node (ref "U4") (pin "32") (pinfunction "TCK_32") (pintype "passive"))
      (node (ref "U4") (pin "33") (pinfunction "VDD33IO_4_33") (pintype "power_in"))
      (node (ref "U4") (pin "39") (pinfunction "VDD33IO_5_39") (pintype "power_in"))
      (node (ref "U4") (pin "40") (pinfunction "TEST3_40") (pintype "passive"))
      (node (ref "U4") (pin "46") (pinfunction "VDD33IO_46") (pintype "power_in"))
      (node (ref "U5") (pin "24") (pinfunction "NRESET_24") (pintype "input"))
      (node (ref "U5") (pin "25") (pinfunction "VDD33IO_25") (pintype "power_in"))
      (node (ref "U5") (pin "35") (pinfunction "VDD33IO_4_35") (pintype "power_in"))
      (node (ref "U5") (pin "48") (pinfunction "VDD33IO_2_48") (pintype "power_in"))
      (node (ref "U5") (pin "49") (pinfunction "TEST1_49") (pintype "power_in"))
      (node (ref "U5") (pin "51") (pinfunction "VDD33IO_3_51") (pintype "power_in"))
      (node (ref "U5") (pin "52") (pinfunction "VDD33IO_52") (pintype "power_in"))
    )
    (net (code "3") (name "/5V0") (class "Default")
      (node (ref "C2") (pin "1") (pinfunction "1_1") (pintype "passive"))
      (node (ref "C3") (pin "+") (pinfunction "+_+") (pintype "passive"))
      (node (ref "C4") (pin "+") (pinfunction "+_+") (pintype "passive"))
      (node (ref "C77") (pin "2") (pinfunction "2_2") (pintype "passive"))
      (node (ref "U$1") (pin "3") (pinfunction "VO_3") (pintype "passive"))
      (node (ref "U1") (pin "102") (pinfunction "VDD5V_102") (pintype "power_in"))
      (node (ref "U6") (pin "7") (pinfunction "IN_7") (pintype "input"))
    )
    (net (code "4") (name "/AUART1_RX") (class "Default")
      (node (ref "JP1") (pin "4") (pinfunction "4_4") (pintype "passive"))
      (node (ref "U1") (pin "128") (pinfunction "I2C_SDA/GPMI_CE2N/AUART1_RX_128") (pintype "bidirectional"))
    )
    (net (code "5") (name "/AUART1_TX") (class "Default")
      (node (ref "JP1") (pin "3") (pinfunction "3_3") (pintype "passive"))
      (node (ref "U1") (pin "127") (pinfunction "I2C_SCL/GPMI_RDY2/AUART1_TX_127") (pintype "bidirectional"))
    )
    (net (code "6") (name "/DCDC_BATTERY") (class "Default")
      (node (ref "C30") (pin "1") (pinfunction "1_1") (pintype "passive"))
      (node (ref "C31") (pin "1") (pinfunction "1_1") (pintype "passive"))
      (node (ref "C32") (pin "1") (pinfunction "1_1") (pintype "passive"))
      (node (ref "C33") (pin "1") (pinfunction "1_1") (pintype "passive"))
      (node (ref "D1") (pin "A") (pinfunction "A_A") (pintype "passive"))
      (node (ref "U1") (pin "100") (pinfunction "DCDC_BATTERY_100") (pintype "power_in"))
      (node (ref "U1") (pin "103") (pinfunction "BATT_103") (pintype "input"))
    )
    (net (code "7") (name "/DCDC_VDDA") (class "Default")
      (node (ref "C26") (pin "1") (pinfunction "1_1") (pintype "passive"))
      (node (ref "C27") (pin "1") (pinfunction "1_1") (pintype "passive"))
      (node (ref "C28") (pin "1") (pinfunction "1_1") (pintype "passive"))
      (node (ref "C29") (pin "1") (pinfunction "1_1") (pintype "passive"))
      (node (ref "C37") (pin "1") (pinfunction "1_1") (pintype "passive"))
      (node (ref "C38") (pin "1") (pinfunction "1_1") (pintype "passive"))
      (node (ref "U1") (pin "110") (pinfunction "VDDA1_110") (pintype "power_in"))
      (node (ref "U1") (pin "96") (pinfunction "DCDC_VDDA_96") (pintype "power_in"))
    )
    (net (code "8") (name "/DCDC_VDDD") (class "Default")
      (node (ref "C18") (pin "1") (pinfunction "1_1") (pintype "passive"))
      (node (ref "C19") (pin "1") (pinfunction "1_1") (pintype "passive"))
      (node (ref "C20") (pin "1") (pinfunction "1_1") (pintype "passive"))
      (node (ref "C21") (pin "1") (pinfunction "1_1") (pintype "passive"))
      (node (ref "U1") (pin "94") (pinfunction "DCDC_VDDD_94") (pintype "power_in"))
    )
    (net (code "9") (name "/DCDC_VDDIO") (class "Default")
      (node (ref "C22") (pin "1") (pinfunction "1_1") (pintype "passive"))
      (node (ref "C23") (pin "1") (pinfunction "1_1") (pintype "passive"))
      (node (ref "C24") (pin "1") (pinfunction "1_1") (pintype "passive"))
      (node (ref "C25") (pin "1") (pinfunction "1_1") (pintype "passive"))
      (node (ref "U1") (pin "95") (pinfunction "DCDC_VDDIO_95") (pintype "power_in"))
    )
    (net (code "10") (name "/DEBUG") (class "Default")
      (node (ref "R7") (pin "2") (pinfunction "2_2") (pintype "passive"))
      (node (ref "U1") (pin "89") (pinfunction "DEBUG_89") (pintype "bidirectional"))
    )
    (net (code "11") (name "/DUART_RX") (class "Default")
      (node (ref "JP1") (pin "1") (pinfunction "1_1") (pintype "passive"))
      (node (ref "U1") (pin "125") (pinfunction "PWM0/ROTARYA/DUART_RX_125") (pintype "bidirectional"))
    )
    (net (code "12") (name "/DUART_TX") (class "Default")
      (node (ref "JP1") (pin "2") (pinfunction "2_2") (pintype "passive"))
      (node (ref "U1") (pin "126") (pinfunction "PWM1/ROTARYB/DUART_TX_126") (pintype "bidirectional"))
    )
    (net (code "13") (name "/EMI_A00") (class "Default")
      (node (ref "U1") (pin "76") (pinfunction "EMI_A00_76") (pintype "bidirectional"))
      (node (ref "U2") (pin "29") (pinfunction "A0_29") (pintype "input"))
    )
    (net (code "14") (name "/EMI_A01") (class "Default")
      (node (ref "U1") (pin "75") (pinfunction "EMI_A01_75") (pintype "bidirectional"))
      (node (ref "U2") (pin "30") (pinfunction "A1_30") (pintype "input"))
    )
    (net (code "15") (name "/EMI_A02") (class "Default")
      (node (ref "U1") (pin "74") (pinfunction "EMI_A02_74") (pintype "bidirectional"))
      (node (ref "U2") (pin "31") (pinfunction "A2_31") (pintype "input"))
    )
    (net (code "16") (name "/EMI_A03") (class "Default")
      (node (ref "U1") (pin "73") (pinfunction "EMI_A03_73") (pintype "bidirectional"))
      (node (ref "U2") (pin "32") (pinfunction "A3_32") (pintype "input"))
    )
    (net (code "17") (name "/EMI_A04") (class "Default")
      (node (ref "U1") (pin "72") (pinfunction "EMI_A04_72") (pintype "bidirectional"))
      (node (ref "U2") (pin "35") (pinfunction "A4_35") (pintype "input"))
    )
    (net (code "18") (name "/EMI_A05") (class "Default")
      (node (ref "U1") (pin "71") (pinfunction "EMI_A05_71") (pintype "bidirectional"))
      (node (ref "U2") (pin "36") (pinfunction "A5_36") (pintype "input"))
    )
    (net (code "19") (name "/EMI_A06") (class "Default")
      (node (ref "U1") (pin "70") (pinfunction "EMI_A06_70") (pintype "bidirectional"))
      (node (ref "U2") (pin "37") (pinfunction "A6_37") (pintype "input"))
    )
    (net (code "20") (name "/EMI_A07") (class "Default")
      (node (ref "U1") (pin "69") (pinfunction "EMI_A07_69") (pintype "bidirectional"))
      (node (ref "U2") (pin "38") (pinfunction "A7_38") (pintype "input"))
    )
    (net (code "21") (name "/EMI_A08") (class "Default")
      (node (ref "U1") (pin "68") (pinfunction "EMI_A08_68") (pintype "bidirectional"))
      (node (ref "U2") (pin "39") (pinfunction "A8_39") (pintype "input"))
    )
    (net (code "22") (name "/EMI_A09") (class "Default")
      (node (ref "U1") (pin "67") (pinfunction "EMI_A09_67") (pintype "bidirectional"))
      (node (ref "U2") (pin "40") (pinfunction "A9_40") (pintype "input"))
    )
    (net (code "23") (name "/EMI_A10") (class "Default")
      (node (ref "U1") (pin "66") (pinfunction "EMI_A10_66") (pintype "bidirectional"))
      (node (ref "U2") (pin "28") (pinfunction "A10/AP_28") (pintype "input"))
    )
    (net (code "24") (name "/EMI_A11") (class "Default")
      (node (ref "U1") (pin "65") (pinfunction "EMI_A11_65") (pintype "bidirectional"))
      (node (ref "U2") (pin "41") (pinfunction "A11_41") (pintype "input"))
    )
    (net (code "25") (name "/EMI_A12") (class "Default")
      (node (ref "U1") (pin "64") (pinfunction "EMI_A12_64") (pintype "bidirectional"))
      (node (ref "U2") (pin "42") (pinfunction "A12_42") (pintype "input"))
    )
    (net (code "26") (name "/EMI_BA0") (class "Default")
      (node (ref "U1") (pin "79") (pinfunction "EMI_BA0_79") (pintype "output"))
      (node (ref "U2") (pin "26") (pinfunction "BA0_26") (pintype "input"))
    )
    (net (code "27") (name "/EMI_BA1") (class "Default")
      (node (ref "U1") (pin "80") (pinfunction "EMI_BA1_80") (pintype "output"))
      (node (ref "U2") (pin "27") (pinfunction "BA1_27") (pintype "input"))
    )
    (net (code "28") (name "/EMI_CASN") (class "Default")
      (node (ref "U1") (pin "61") (pinfunction "EMI_CASN_61") (pintype "output"))
      (node (ref "U2") (pin "22") (pinfunction "#CAS_22") (pintype "input"))
    )
    (net (code "29") (name "/EMI_CE0N") (class "Default")
      (node (ref "R18") (pin "1") (pinfunction "1_1") (pintype "passive"))
      (node (ref "U1") (pin "63") (pinfunction "EMI_CE0N_63") (pintype "output"))
      (node (ref "U2") (pin "24") (pinfunction "#CS_24") (pintype "input"))
    )
    (net (code "30") (name "/EMI_CKE") (class "Default")
      (node (ref "U1") (pin "78") (pinfunction "EMI_CKE_78") (pintype "output"))
      (node (ref "U2") (pin "44") (pinfunction "CKE_44") (pintype "input"))
    )
    (net (code "31") (name "/EMI_CLK") (class "Default")
      (node (ref "U1") (pin "36") (pinfunction "EMI_CLK_36") (pintype "output"))
      (node (ref "U2") (pin "45") (pinfunction "CK_45") (pintype "input"))
    )
    (net (code "32") (name "/EMI_CLKN") (class "Default")
      (node (ref "U1") (pin "37") (pinfunction "EMI_CLKN_37") (pintype "output"))
      (node (ref "U2") (pin "46") (pinfunction "#CK_46") (pintype "input"))
    )
    (net (code "33") (name "/EMI_D00") (class "Default")
      (node (ref "U1") (pin "41") (pinfunction "EMI_D00_41") (pintype "bidirectional"))
      (node (ref "U2") (pin "2") (pinfunction "DQ0_2") (pintype "bidirectional"))
    )
    (net (code "34") (name "/EMI_D01") (class "Default")
      (node (ref "U1") (pin "43") (pinfunction "EMI_D01_43") (pintype "bidirectional"))
      (node (ref "U2") (pin "4") (pinfunction "DQ1_4") (pintype "bidirectional"))
    )
    (net (code "35") (name "/EMI_D02") (class "Default")
      (node (ref "U1") (pin "42") (pinfunction "EMI_D02_42") (pintype "bidirectional"))
      (node (ref "U2") (pin "5") (pinfunction "DQ2_5") (pintype "bidirectional"))
    )
    (net (code "36") (name "/EMI_D03") (class "Default")
      (node (ref "U1") (pin "44") (pinfunction "EMI_D03_44") (pintype "bidirectional"))
      (node (ref "U2") (pin "7") (pinfunction "DQ3_7") (pintype "bidirectional"))
    )
    (net (code "37") (name "/EMI_D04") (class "Default")
      (node (ref "U1") (pin "47") (pinfunction "EMI_D04_47") (pintype "bidirectional"))
      (node (ref "U2") (pin "8") (pinfunction "DQ4_8") (pintype "bidirectional"))
    )
    (net (code "38") (name "/EMI_D05") (class "Default")
      (node (ref "U1") (pin "48") (pinfunction "EMI_D05_48") (pintype "bidirectional"))
      (node (ref "U2") (pin "10") (pinfunction "DQ5_10") (pintype "bidirectional"))
    )
    (net (code "39") (name "/EMI_D06") (class "Default")
      (node (ref "U1") (pin "49") (pinfunction "EMI_D06_49") (pintype "bidirectional"))
      (node (ref "U2") (pin "11") (pinfunction "DQ6_11") (pintype "bidirectional"))
    )
    (net (code "40") (name "/EMI_D07") (class "Default")
      (node (ref "U1") (pin "50") (pinfunction "EMI_D07_50") (pintype "bidirectional"))
      (node (ref "U2") (pin "13") (pinfunction "DQ7_13") (pintype "bidirectional"))
    )
    (net (code "41") (name "/EMI_D08") (class "Default")
      (node (ref "U1") (pin "51") (pinfunction "EMI_D08_51") (pintype "bidirectional"))
      (node (ref "U2") (pin "54") (pinfunction "DQ8_54") (pintype "bidirectional"))
    )
    (net (code "42") (name "/EMI_D09") (class "Default")
      (node (ref "U1") (pin "52") (pinfunction "EMI_D09_52") (pintype "bidirectional"))
      (node (ref "U2") (pin "56") (pinfunction "DQ9_56") (pintype "bidirectional"))
    )
    (net (code "43") (name "/EMI_D10") (class "Default")
      (node (ref "U1") (pin "54") (pinfunction "EMI_D10_54") (pintype "bidirectional"))
      (node (ref "U2") (pin "57") (pinfunction "DQ10_57") (pintype "bidirectional"))
    )
    (net (code "44") (name "/EMI_D11") (class "Default")
      (node (ref "U1") (pin "55") (pinfunction "EMI_D11_55") (pintype "bidirectional"))
      (node (ref "U2") (pin "59") (pinfunction "DQ11_59") (pintype "bidirectional"))
    )
    (net (code "45") (name "/EMI_D12") (class "Default")
      (node (ref "U1") (pin "57") (pinfunction "EMI_D12_57") (pintype "bidirectional"))
      (node (ref "U2") (pin "60") (pinfunction "DQ12_60") (pintype "bidirectional"))
    )
    (net (code "46") (name "/EMI_D13") (class "Default")
      (node (ref "U1") (pin "58") (pinfunction "EMI_D13_58") (pintype "bidirectional"))
      (node (ref "U2") (pin "62") (pinfunction "DQ13_62") (pintype "bidirectional"))
    )
    (net (code "47") (name "/EMI_D14") (class "Default")
      (node (ref "U1") (pin "60") (pinfunction "EMI_D14_60") (pintype "bidirectional"))
      (node (ref "U2") (pin "63") (pinfunction "DQ14_63") (pintype "bidirectional"))
    )
    (net (code "48") (name "/EMI_D15") (class "Default")
      (node (ref "U1") (pin "59") (pinfunction "EMI_D15_59") (pintype "bidirectional"))
      (node (ref "U2") (pin "65") (pinfunction "DQ15_65") (pintype "bidirectional"))
    )
    (net (code "49") (name "/EMI_DQM0") (class "Default")
      (node (ref "U1") (pin "46") (pinfunction "EMI_DQM0_46") (pintype "output"))
      (node (ref "U2") (pin "20") (pinfunction "LDM_20") (pintype "input"))
    )
    (net (code "50") (name "/EMI_DQM1") (class "Default")
      (node (ref "U1") (pin "56") (pinfunction "EMI_DQM1_56") (pintype "output"))
      (node (ref "U2") (pin "47") (pinfunction "UDM_47") (pintype "input"))
    )
    (net (code "51") (name "/EMI_DQS0") (class "Default")
      (node (ref "U1") (pin "39") (pinfunction "EMI_DQS0_39") (pintype "output"))
      (node (ref "U2") (pin "16") (pinfunction "LDQS_16") (pintype "bidirectional"))
    )
    (net (code "52") (name "/EMI_DQS1") (class "Default")
      (node (ref "U1") (pin "40") (pinfunction "EMI_DQS1_40") (pintype "output"))
      (node (ref "U2") (pin "51") (pinfunction "UDQS_51") (pintype "input"))
    )
    (net (code "53") (name "/EMI_RASN") (class "Default")
      (node (ref "U1") (pin "62") (pinfunction "EMI_RASN_62") (pintype "output"))
      (node (ref "U2") (pin "23") (pinfunction "#RAS_23") (pintype "input"))
    )
    (net (code "54") (name "/EMI_WEN") (class "Default")
      (node (ref "U1") (pin "77") (pinfunction "EMI_WEN_77") (pintype "output"))
      (node (ref "U2") (pin "21") (pinfunction "#WE_21") (pintype "input"))
    )
    (net (code "55") (name "/GPMI_ALE") (class "Default")
      (node (ref "U1") (pin "20") (pinfunction "GPMI_ALE/LCD_D17_20") (pintype "bidirectional"))
      (node (ref "U3") (pin "17") (pinfunction "ALE_17") (pintype "input"))
    )
    (net (code "56") (name "/GPMI_CE0N") (class "Default")
      (node (ref "R14") (pin "1") (pinfunction "1_1") (pintype "passive"))
      (node (ref "U1") (pin "82") (pinfunction "GPMI_CE0N_82") (pintype "bidirectional"))
      (node (ref "U3") (pin "9") (pinfunction "#CE_9") (pintype "input"))
    )
    (net (code "57") (name "/GPMI_CLE") (class "Default")
      (node (ref "U1") (pin "19") (pinfunction "GPMI_CLE/LCD_D16_19") (pintype "bidirectional"))
      (node (ref "U3") (pin "16") (pinfunction "CLE_16") (pintype "input"))
    )
    (net (code "58") (name "/GPMI_D00") (class "Default")
      (node (ref "U1") (pin "22") (pinfunction "GPMI_D00/LCD_D08/SSP2_DATA0_22") (pintype "bidirectional"))
      (node (ref "U3") (pin "29") (pinfunction "I/O0_29") (pintype "bidirectional"))
    )
    (net (code "59") (name "/GPMI_D01") (class "Default")
      (node (ref "U1") (pin "23") (pinfunction "GPMI_D01/LCD_D09/SSP2_DATA1_23") (pintype "bidirectional"))
      (node (ref "U3") (pin "30") (pinfunction "I/O1_30") (pintype "bidirectional"))
    )
    (net (code "60") (name "/GPMI_D02") (class "Default")
      (node (ref "U1") (pin "24") (pinfunction "GPMI_D02/LCD_D10/SSP2_DATA2_24") (pintype "bidirectional"))
      (node (ref "U3") (pin "31") (pinfunction "I/O2_31") (pintype "bidirectional"))
    )
    (net (code "61") (name "/GPMI_D03") (class "Default")
      (node (ref "U1") (pin "25") (pinfunction "GPMI_D03/LCD_D11/SSP2_DATA3_25") (pintype "bidirectional"))
      (node (ref "U3") (pin "32") (pinfunction "I/O3_32") (pintype "bidirectional"))
    )
    (net (code "62") (name "/GPMI_D04") (class "Default")
      (node (ref "U1") (pin "27") (pinfunction "GPMI_D04/LCD_D12/SSP2_DATA4_27") (pintype "bidirectional"))
      (node (ref "U3") (pin "41") (pinfunction "I/O4_41") (pintype "bidirectional"))
    )
    (net (code "63") (name "/GPMI_D05") (class "Default")
      (node (ref "U1") (pin "26") (pinfunction "GPMI_D05/LCD_D13/SSP2_DATA5_26") (pintype "bidirectional"))
      (node (ref "U3") (pin "42") (pinfunction "I/O5_42") (pintype "bidirectional"))
    )
    (net (code "64") (name "/GPMI_D06") (class "Default")
      (node (ref "U1") (pin "29") (pinfunction "GPMI_D06/LCD_D14/SSP2_DATA6_29") (pintype "bidirectional"))
      (node (ref "U3") (pin "43") (pinfunction "I/O6_43") (pintype "bidirectional"))
    )
    (net (code "65") (name "/GPMI_D07") (class "Default")
      (node (ref "U1") (pin "28") (pinfunction "GPMI_D07/LCD_D15/SSP2_DATA7_28") (pintype "bidirectional"))
      (node (ref "U3") (pin "44") (pinfunction "I/O7_44") (pintype "bidirectional"))
    )
    (net (code "66") (name "/GPMI_RDN") (class "Default")
      (node (ref "U1") (pin "31") (pinfunction "GPMI_RDN_31") (pintype "bidirectional"))
      (node (ref "U3") (pin "8") (pinfunction "#RE_8") (pintype "input"))
    )
    (net (code "67") (name "/GPMI_RDY0") (class "Default")
      (node (ref "R13") (pin "1") (pinfunction "1_1") (pintype "passive"))
      (node (ref "U1") (pin "32") (pinfunction "GPMI_RDY0/SSP2_DETECT_32") (pintype "bidirectional"))
      (node (ref "U3") (pin "7") (pinfunction "R/#B_7") (pintype "output"))
    )
    (net (code "68") (name "/GPMI_WPN") (class "Default")
      (node (ref "R15") (pin "2") (pinfunction "2_2") (pintype "passive"))
      (node (ref "U1") (pin "34") (pinfunction "GPMI_WPN_34") (pintype "bidirectional"))
      (node (ref "U3") (pin "19") (pinfunction "#WP_19") (pintype "input"))
    )
    (net (code "69") (name "/GPMI_WRN") (class "Default")
      (node (ref "U1") (pin "33") (pinfunction "GPMI_WRN/SSP2_SCK_33") (pintype "bidirectional"))
      (node (ref "U3") (pin "18") (pinfunction "#WE_18") (pintype "input"))
    )
    (net (code "70") (name "/HP_VGND") (class "Default")
      (node (ref "U1") (pin "111") (pinfunction "HP_VGND_111") (pintype "power_in"))
    )
    (net (code "71") (name "/I2C_SCL") (class "Default")
      (node (ref "U1") (pin "11") (pinfunction "LCD_ENABLE/I2C_SCL_11") (pintype "bidirectional"))
    )
    (net (code "72") (name "/I2C_SDA") (class "Default")
      (node (ref "U1") (pin "15") (pinfunction "LCD_HSYNC/I2C_SDA_15") (pintype "bidirectional"))
    )
    (net (code "73") (name "/LCD_D00") (class "Default")
      (node (ref "R23") (pin "2") (pinfunction "2_2") (pintype "passive"))
      (node (ref "R27") (pin "2") (pinfunction "2_2") (pintype "passive"))
      (node (ref "U1") (pin "2") (pinfunction "LCD_D00_2") (pintype "bidirectional"))
    )
    (net (code "74") (name "/LCD_D01") (class "Default")
      (node (ref "R22") (pin "2") (pinfunction "2_2") (pintype "passive"))
      (node (ref "R26") (pin "2") (pinfunction "2_2") (pintype "passive"))
      (node (ref "U1") (pin "3") (pinfunction "LCD_D01_3") (pintype "bidirectional"))
    )
    (net (code "75") (name "/LCD_D02") (class "Default")
      (node (ref "R21") (pin "2") (pinfunction "2_2") (pintype "passive"))
      (node (ref "R25") (pin "2") (pinfunction "2_2") (pintype "passive"))
      (node (ref "U1") (pin "4") (pinfunction "LCD_D02_4") (pintype "bidirectional"))
    )
    (net (code "76") (name "/LCD_D03") (class "Default")
      (node (ref "R20") (pin "2") (pinfunction "2_2") (pintype "passive"))
      (node (ref "R24") (pin "2") (pinfunction "2_2") (pintype "passive"))
      (node (ref "U1") (pin "5") (pinfunction "LCD_D03_5") (pintype "bidirectional"))
    )
    (net (code "77") (name "/NFDX_LED") (class "Default")
      (node (ref "LED1") (pin "C") (pinfunction "C_C") (pintype "passive"))
      (node (ref "U4") (pin "20") (pinfunction "NFDX_LED/GPIO0_20") (pintype "bidirectional"))
    )
    (net (code "78") (name "/NFDX_LED_2") (class "Default")
      (node (ref "LED4") (pin "C") (pinfunction "C_C") (pintype "passive"))
      (node (ref "U5") (pin "26") (pinfunction "NFDX_LED/GPIO8_26") (pintype "bidirectional"))
    )
    (net (code "79") (name "/NLNKA_LED") (class "Default")
      (node (ref "RJ1") (pin "Y+") (pinfunction "Y+_Y+") (pintype "bidirectional"))
      (node (ref "U4") (pin "21") (pinfunction "NLNKA_LED/GPIO1_21") (pintype "bidirectional"))
    )
    (net (code "80") (name "/NLNKA_LED_2") (class "Default")
      (node (ref "RJ2") (pin "Y+") (pinfunction "Y+_Y+") (pintype "bidirectional"))
      (node (ref "U5") (pin "27") (pinfunction "NLNKA_LED/GPIO9_27") (pintype "bidirectional"))
    )
    (net (code "81") (name "/NSPD_LED") (class "Default")
      (node (ref "RJ1") (pin "G+") (pinfunction "G+_G+") (pintype "bidirectional"))
      (node (ref "U4") (pin "22") (pinfunction "NSPD_LED/GPIO2_22") (pintype "bidirectional"))
    )
    (net (code "82") (name "/NSPD_LED_2") (class "Default")
      (node (ref "RJ2") (pin "G+") (pinfunction "G+_G+") (pintype "bidirectional"))
      (node (ref "U5") (pin "28") (pinfunction "NSPD_LED/GPIO10_28") (pintype "bidirectional"))
    )
    (net (code "83") (name "/PRTCTL2") (class "Default")
      (node (ref "U4") (pin "14") (pinfunction "PRTCTL2_14") (pintype "passive"))
      (node (ref "U6") (pin "1") (pinfunction "ENA_1") (pintype "input"))
      (node (ref "U6") (pin "2") (pinfunction "FLAG_A_2") (pintype "open_collector"))
    )
    (net (code "84") (name "/PRTCTL3") (class "Default")
      (node (ref "U4") (pin "16") (pinfunction "PRTCTL3_16") (pintype "passive"))
      (node (ref "U6") (pin "3") (pinfunction "FLAG_B_3") (pintype "open_collector"))
      (node (ref "U6") (pin "4") (pinfunction "ENB_4") (pintype "input"))
    )
    (net (code "85") (name "/PSWITCH") (class "Default")
      (node (ref "C5") (pin "1") (pinfunction "1_1") (pintype "passive"))
      (node (ref "R2") (pin "2") (pinfunction "2_2") (pintype "passive"))
      (node (ref "U1") (pin "119") (pinfunction "PSWITCH_119") (pintype "input"))
    )
    (net (code "86") (name "/RXN") (class "Default")
      (node (ref "C72") (pin "1") (pinfunction "1_1") (pintype "passive"))
      (node (ref "R29") (pin "2") (pinfunction "2_2") (pintype "passive"))
      (node (ref "RJ1") (pin "RD-") (pinfunction "RD-_RD-") (pintype "bidirectional"))
      (node (ref "U4") (pin "53") (pinfunction "RXN_53") (pintype "passive"))
    )
    (net (code "87") (name "/RXN_2") (class "Default")
      (node (ref "C81") (pin "1") (pinfunction "1_1") (pintype "passive"))
      (node (ref "R45") (pin "2") (pinfunction "2_2") (pintype "passive"))
      (node (ref "RJ2") (pin "RD-") (pinfunction "RD-_RD-") (pintype "bidirectional"))
      (node (ref "U5") (pin "5") (pinfunction "RXN_5") (pintype "bidirectional"))
    )
    (net (code "88") (name "/RXP") (class "Default")
      (node (ref "C70") (pin "1") (pinfunction "1_1") (pintype "passive"))
      (node (ref "R30") (pin "2") (pinfunction "2_2") (pintype "passive"))
      (node (ref "RJ1") (pin "RD+") (pinfunction "RD+_RD+") (pintype "bidirectional"))
      (node (ref "U4") (pin "52") (pinfunction "RXP_52") (pintype "passive"))
    )
    (net (code "89") (name "/RXP_2") (class "Default")
      (node (ref "C79") (pin "1") (pinfunction "1_1") (pintype "passive"))
      (node (ref "R46") (pin "2") (pinfunction "2_2") (pintype "passive"))
      (node (ref "RJ2") (pin "RD+") (pinfunction "RD+_RD+") (pintype "bidirectional"))
      (node (ref "U5") (pin "6") (pinfunction "RXP_6") (pintype "bidirectional"))
    )
    (net (code "90") (name "/SSP1_CMD") (class "Default")
      (node (ref "R11") (pin "1") (pinfunction "1_1") (pintype "passive"))
      (node (ref "SD/MMC1") (pin "3") (pinfunction "CMD/DI_3") (pintype "input"))
      (node (ref "U1") (pin "83") (pinfunction "SSP1_CMD/SPI1_MOSI/JTAG_TDO_83") (pintype "bidirectional"))
    )
    (net (code "91") (name "/SSP1_DATA0") (class "Default")
      (node (ref "R10") (pin "1") (pinfunction "1_1") (pintype "passive"))
      (node (ref "SD/MMC1") (pin "7") (pinfunction "DAT0/DO_7") (pintype "output"))
      (node (ref "U1") (pin "84") (pinfunction "SSP1_DATA0/SPI1_MISO/JTAG_TDI_84") (pintype "bidirectional"))
    )
    (net (code "92") (name "/SSP1_DATA1") (class "Default")
      (node (ref "R9") (pin "1") (pinfunction "1_1") (pintype "passive"))
      (node (ref "SD/MMC1") (pin "8") (pinfunction "DAT1/RES_8") (pintype "bidirectional"))
      (node (ref "U1") (pin "85") (pinfunction "SSP1_DATA1/I2C_SCL/JTAG_TCLK_85") (pintype "bidirectional"))
    )
    (net (code "93") (name "/SSP1_DATA2") (class "Default")
      (node (ref "R8") (pin "1") (pinfunction "1_1") (pintype "passive"))
      (node (ref "SD/MMC1") (pin "1") (pinfunction "DAT2/RES_1") (pintype "bidirectional"))
      (node (ref "U1") (pin "86") (pinfunction "SSP1_DATA2/I2C_SDA/JTAG_RTCK_86") (pintype "bidirectional"))
    )
    (net (code "94") (name "/SSP1_DATA3") (class "Default")
      (node (ref "R12") (pin "2") (pinfunction "2_2") (pintype "passive"))
      (node (ref "SD/MMC1") (pin "2") (pinfunction "CD/DAT3/CS_2") (pintype "input"))
      (node (ref "U1") (pin "87") (pinfunction "SSP1_DATA3/SPI1_SS#/JTAG_TMS_87") (pintype "bidirectional"))
    )
    (net (code "95") (name "/SSP1_SCK") (class "Default")
      (node (ref "SD/MMC1") (pin "5") (pinfunction "CLK/SCLK_5") (pintype "input"))
      (node (ref "U1") (pin "90") (pinfunction "SSP1_SCK/SPI1_SCK/JTAG_TRST_90") (pintype "bidirectional"))
    )
    (net (code "96") (name "/TXN") (class "Default")
      (node (ref "C69") (pin "1") (pinfunction "1_1") (pintype "passive"))
      (node (ref "R31") (pin "2") (pinfunction "2_2") (pintype "passive"))
      (node (ref "RJ1") (pin "TD-") (pinfunction "TD-_TD-") (pintype "bidirectional"))
      (node (ref "U4") (pin "56") (pinfunction "TXN_56") (pintype "passive"))
    )
    (net (code "97") (name "/TXN_2") (class "Default")
      (node (ref "C78") (pin "1") (pinfunction "1_1") (pintype "passive"))
      (node (ref "R47") (pin "2") (pinfunction "2_2") (pintype "passive"))
      (node (ref "RJ2") (pin "TD-") (pinfunction "TD-_TD-") (pintype "bidirectional"))
      (node (ref "U5") (pin "2") (pinfunction "TXN_2") (pintype "bidirectional"))
    )
    (net (code "98") (name "/TXP") (class "Default")
      (node (ref "C71") (pin "1") (pinfunction "1_1") (pintype "passive"))
      (node (ref "R32") (pin "2") (pinfunction "2_2") (pintype "passive"))
      (node (ref "RJ1") (pin "TD+") (pinfunction "TD+_TD+") (pintype "bidirectional"))
      (node (ref "U4") (pin "55") (pinfunction "TXP_55") (pintype "passive"))
    )
    (net (code "99") (name "/TXP_2") (class "Default")
      (node (ref "C80") (pin "1") (pinfunction "1_1") (pintype "passive"))
      (node (ref "R48") (pin "2") (pinfunction "2_2") (pintype "passive"))
      (node (ref "RJ2") (pin "TD+") (pinfunction "TD+_TD+") (pintype "bidirectional"))
      (node (ref "U5") (pin "3") (pinfunction "TXP_3") (pintype "bidirectional"))
    )
    (net (code "100") (name "/USB_DM") (class "Default")
      (node (ref "U1") (pin "123") (pinfunction "USB_DM_123") (pintype "bidirectional"))
      (node (ref "U4") (pin "58") (pinfunction "USBDM0_58") (pintype "passive"))
    )
    (net (code "101") (name "/USB_DM2") (class "Default")
      (node (ref "U4") (pin "1") (pinfunction "USBDM2_1") (pintype "passive"))
      (node (ref "X1") (pin "2") (pinfunction "2_2") (pintype "passive"))
    )
    (net (code "102") (name "/USB_DM3") (class "Default")
      (node (ref "U4") (pin "3") (pinfunction "USBDM3_3") (pintype "passive"))
      (node (ref "U5") (pin "11") (pinfunction "USBDM_11") (pintype "bidirectional"))
    )
    (net (code "103") (name "/USB_DP") (class "Default")
      (node (ref "U1") (pin "124") (pinfunction "USB_DP_124") (pintype "bidirectional"))
      (node (ref "U4") (pin "59") (pinfunction "USBDP0_59") (pintype "passive"))
    )
    (net (code "104") (name "/USB_DP2") (class "Default")
      (node (ref "U4") (pin "2") (pinfunction "USBDP2_2") (pintype "passive"))
      (node (ref "X1") (pin "3") (pinfunction "3_3") (pintype "passive"))
    )
    (net (code "105") (name "/USB_DP3") (class "Default")
      (node (ref "U4") (pin "4") (pinfunction "USBDP3_4") (pintype "passive"))
      (node (ref "U5") (pin "12") (pinfunction "USBDP_12") (pintype "bidirectional"))
    )
    (net (code "106") (name "/USB_PWRA") (class "Default")
      (node (ref "R41") (pin "2") (pinfunction "2_2") (pintype "passive"))
      (node (ref "U6") (pin "8") (pinfunction "OUT_A_8") (pintype "output"))
      (node (ref "X1") (pin "1") (pinfunction "1_1") (pintype "passive"))
    )
    (net (code "107") (name "/USB_PWRB") (class "Default")
      (node (ref "R40") (pin "2") (pinfunction "2_2") (pintype "passive"))
      (node (ref "U6") (pin "5") (pinfunction "OUT_B_5") (pintype "output"))
    )
    (net (code "108") (name "/VDD3V3A") (class "Default")
      (node (ref "C54") (pin "1") (pinfunction "1_1") (pintype "passive"))
      (node (ref "C55") (pin "1") (pinfunction "1_1") (pintype "passive"))
      (node (ref "C56") (pin "1") (pinfunction "1_1") (pintype "passive"))
      (node (ref "C57") (pin "1") (pinfunction "1_1") (pintype "passive"))
      (node (ref "C58") (pin "1") (pinfunction "1_1") (pintype "passive"))
      (node (ref "C7") (pin "1") (pinfunction "1_1") (pintype "passive"))
      (node (ref "C8") (pin "1") (pinfunction "1_1") (pintype "passive"))
      (node (ref "C86") (pin "1") (pinfunction "1_1") (pintype "passive"))
      (node (ref "C87") (pin "1") (pinfunction "1_1") (pintype "passive"))
      (node (ref "C88") (pin "1") (pinfunction "1_1") (pintype "passive"))
      (node (ref "C89") (pin "1") (pinfunction "1_1") (pintype "passive"))
      (node (ref "L1") (pin "2") (pinfunction "2_2") (pintype "passive"))
      (node (ref "L6") (pin "2") (pinfunction "2_2") (pintype "passive"))
      (node (ref "R28") (pin "1") (pinfunction "1_1") (pintype "passive"))
      (node (ref "R29") (pin "1") (pinfunction "1_1") (pintype "passive"))
      (node (ref "R30") (pin "1") (pinfunction "1_1") (pintype "passive"))
      (node (ref "R31") (pin "1") (pinfunction "1_1") (pintype "passive"))
      (node (ref "R32") (pin "1") (pinfunction "1_1") (pintype "passive"))
      (node (ref "R44") (pin "1") (pinfunction "1_1") (pintype "passive"))
      (node (ref "R45") (pin "1") (pinfunction "1_1") (pintype "passive"))
      (node (ref "R46") (pin "1") (pinfunction "1_1") (pintype "passive"))
      (node (ref "R47") (pin "1") (pinfunction "1_1") (pintype "passive"))
      (node (ref "R48") (pin "1") (pinfunction "1_1") (pintype "passive"))
      (node (ref "U4") (pin "10") (pinfunction "VDD33A_3_10") (pintype "power_in"))
      (node (ref "U4") (pin "49") (pinfunction "VDD33A_4_49") (pintype "power_in"))
      (node (ref "U4") (pin "5") (pinfunction "VDD33A_2_5") (pintype "power_in"))
      (node (ref "U4") (pin "51") (pinfunction "VDD33A_5_51") (pintype "power_in"))
      (node (ref "U4") (pin "54") (pinfunction "VDD33A_6_54") (pintype "power_in"))
      (node (ref "U4") (pin "57") (pinfunction "VDD33A_7_57") (pintype "power_in"))
      (node (ref "U4") (pin "64") (pinfunction "VDD33A_64") (pintype "power_in"))
      (node (ref "U5") (pin "15") (pinfunction "VDD33A_3_15") (pintype "power_in"))
      (node (ref "U5") (pin "4") (pinfunction "VDD33A_4") (pintype "power_in"))
      (node (ref "U5") (pin "9") (pinfunction "VDD33A_2_9") (pintype "power_in"))
    )
    (net (code "109") (name "/VDD4P2") (class "Default")
      (node (ref "C16") (pin "1") (pinfunction "1_1") (pintype "passive"))
      (node (ref "C17") (pin "1") (pinfunction "1_1") (pintype "passive"))
      (node (ref "D1") (pin "C") (pinfunction "C_C") (pintype "passive"))
      (node (ref "U1") (pin "101") (pinfunction "VDD4P2_101") (pintype "power_in"))
    )
    (net (code "110") (name "/VDD18CORE") (class "Default")
      (node (ref "C59") (pin "1") (pinfunction "1_1") (pintype "passive"))
      (node (ref "C60") (pin "1") (pinfunction "1_1") (pintype "passive"))
      (node (ref "C61") (pin "1") (pinfunction "1_1") (pintype "passive"))
      (node (ref "U4") (pin "15") (pinfunction "VDD18CORE_2_15") (pintype "power_in"))
      (node (ref "U4") (pin "38") (pinfunction "VDD18CORE_38") (pintype "power_in"))
    )
    (net (code "111") (name "/VDD18ETHPLL") (class "Default")
      (node (ref "C67") (pin "1") (pinfunction "1_1") (pintype "passive"))
      (node (ref "L4") (pin "2") (pinfunction "2_2") (pintype "passive"))
      (node (ref "U4") (pin "48") (pinfunction "VDD18ETHPLL_48") (pintype "power_in"))
    )
    (net (code "112") (name "/VDD18USBPLL") (class "Default")
      (node (ref "C68") (pin "1") (pinfunction "1_1") (pintype "passive"))
      (node (ref "L4") (pin "1") (pinfunction "1_1") (pintype "passive"))
      (node (ref "U4") (pin "62") (pinfunction "VDD18USBPLL_62") (pintype "power_in"))
    )
    (net (code "113") (name "/VDDCORE") (class "Default")
      (node (ref "C83") (pin "1") (pinfunction "1_1") (pintype "passive"))
      (node (ref "C95") (pin "1") (pinfunction "1_1") (pintype "passive"))
      (node (ref "C96") (pin "1") (pinfunction "1_1") (pintype "passive"))
      (node (ref "C97") (pin "1") (pinfunction "1_1") (pintype "passive"))
      (node (ref "L5") (pin "1") (pinfunction "1_1") (pintype "passive"))
      (node (ref "L7") (pin "1") (pinfunction "1_1") (pintype "passive"))
      (node (ref "U5") (pin "21") (pinfunction "VDDCORE_21") (pintype "bidirectional"))
      (node (ref "U5") (pin "50") (pinfunction "VDDCORE_50") (pintype "power_in"))
    )
    (net (code "114") (name "/VDDIO_DRAM") (class "Default")
      (node (ref "C13") (pin "1") (pinfunction "1_1") (pintype "passive"))
      (node (ref "C14") (pin "1") (pinfunction "1_1") (pintype "passive"))
      (node (ref "C44") (pin "2") (pinfunction "2_2") (pintype "passive"))
      (node (ref "C45") (pin "2") (pinfunction "2_2") (pintype "passive"))
      (node (ref "C46") (pin "2") (pinfunction "2_2") (pintype "passive"))
      (node (ref "C47") (pin "2") (pinfunction "2_2") (pintype "passive"))
      (node (ref "C48") (pin "2") (pinfunction "2_2") (pintype "passive"))
      (node (ref "C49") (pin "2") (pinfunction "2_2") (pintype "passive"))
      (node (ref "C50") (pin "2") (pinfunction "2_2") (pintype "passive"))
      (node (ref "C51") (pin "2") (pinfunction "2_2") (pintype "passive"))
      (node (ref "C52") (pin "2") (pinfunction "2_2") (pintype "passive"))
      (node (ref "R17") (pin "2") (pinfunction "2_2") (pintype "passive"))
      (node (ref "R18") (pin "2") (pinfunction "2_2") (pintype "passive"))
      (node (ref "U1") (pin "38") (pinfunction "VDDIO_EMIQ_38") (pintype "power_in"))
      (node (ref "U1") (pin "45") (pinfunction "VDDIO_EMI1_45") (pintype "power_in"))
      (node (ref "U1") (pin "53") (pinfunction "VDDIO_EMI2_53") (pintype "power_in"))
      (node (ref "U2") (pin "1") (pinfunction "VDD1_1") (pintype "power_in"))
      (node (ref "U2") (pin "15") (pinfunction "VDDQ3_15") (pintype "power_in"))
      (node (ref "U2") (pin "18") (pinfunction "VDD2_18") (pintype "power_in"))
      (node (ref "U2") (pin "3") (pinfunction "VDDQ1_3") (pintype "power_in"))
      (node (ref "U2") (pin "33") (pinfunction "VDD3_33") (pintype "power_in"))
      (node (ref "U2") (pin "55") (pinfunction "VDDQ4_55") (pintype "power_in"))
      (node (ref "U2") (pin "61") (pinfunction "VDDQ5_61") (pintype "power_in"))
      (node (ref "U2") (pin "9") (pinfunction "VDDQ2_9") (pintype "power_in"))
    )
    (net (code "115") (name "/VDDM{slash}LRADC4") (class "Default")
      (node (ref "C15") (pin "1") (pinfunction "1_1") (pintype "passive"))
      (node (ref "U1") (pin "106") (pinfunction "VDDM/LRADC4_106") (pintype "power_in"))
    )
    (net (code "116") (name "/VDDPLL2") (class "Default")
      (node (ref "C99") (pin "1") (pinfunction "1_1") (pintype "passive"))
      (node (ref "L7") (pin "2") (pinfunction "2_2") (pintype "passive"))
      (node (ref "U5") (pin "10") (pinfunction "VDDPLL_10") (pintype "power_in"))
    )
    (net (code "117") (name "/VDDXTAL") (class "Default")
      (node (ref "C34") (pin "1") (pinfunction "1_1") (pintype "passive"))
      (node (ref "S1") (pin "3") (pinfunction "P_3") (pintype "passive"))
      (node (ref "S1") (pin "4") (pinfunction "P1_4") (pintype "passive"))
      (node (ref "U1") (pin "120") (pinfunction "VDDXTAL_120") (pintype "passive"))
    )
    (net (code "118") (name "/XI") (class "Default")
      (node (ref "C84") (pin "1") (pinfunction "1_1") (pintype "passive"))
      (node (ref "HC49US1") (pin "1") (pinfunction "1_1") (pintype "passive"))
      (node (ref "U5") (pin "18") (pinfunction "XI_18") (pintype "input"))
    )
    (net (code "119") (name "/XTALI") (class "Default")
      (node (ref "C35") (pin "2") (pinfunction "2_2") (pintype "passive"))
      (node (ref "Q1") (pin "2") (pinfunction "2_2") (pintype "passive"))
      (node (ref "T1") (pin "3") (pinfunction "C_3") (pintype "passive"))
      (node (ref "U1") (pin "122") (pinfunction "XTALI_122") (pintype "input"))
    )
    (net (code "120") (name "/XTALO") (class "Default")
      (node (ref "C36") (pin "2") (pinfunction "2_2") (pintype "passive"))
      (node (ref "Q1") (pin "1") (pinfunction "1_1") (pintype "passive"))
      (node (ref "T2") (pin "3") (pinfunction "C_3") (pintype "passive"))
      (node (ref "U1") (pin "121") (pinfunction "XTALO_121") (pintype "output"))
    )
    (net (code "121") (name "GND") (class "Default")
      (node (ref "C1") (pin "2") (pinfunction "2_2") (pintype "passive"))
      (node (ref "C10") (pin "2") (pinfunction "2_2") (pintype "passive"))
      (node (ref "C11") (pin "2") (pinfunction "2_2") (pintype "passive"))
      (node (ref "C12") (pin "2") (pinfunction "2_2") (pintype "passive"))
      (node (ref "C13") (pin "2") (pinfunction "2_2") (pintype "passive"))
      (node (ref "C14") (pin "2") (pinfunction "2_2") (pintype "passive"))
      (node (ref "C15") (pin "2") (pinfunction "2_2") (pintype "passive"))
      (node (ref "C16") (pin "2") (pinfunction "2_2") (pintype "passive"))
      (node (ref "C17") (pin "2") (pinfunction "2_2") (pintype "passive"))
      (node (ref "C18") (pin "2") (pinfunction "2_2") (pintype "passive"))
      (node (ref "C19") (pin "2") (pinfunction "2_2") (pintype "passive"))
      (node (ref "C2") (pin "2") (pinfunction "2_2") (pintype "passive"))
      (node (ref "C20") (pin "2") (pinfunction "2_2") (pintype "passive"))
      (node (ref "C21") (pin "2") (pinfunction "2_2") (pintype "passive"))
      (node (ref "C22") (pin "2") (pinfunction "2_2") (pintype "passive"))
      (node (ref "C23") (pin "2") (pinfunction "2_2") (pintype "passive"))
      (node (ref "C24") (pin "2") (pinfunction "2_2") (pintype "passive"))
      (node (ref "C25") (pin "2") (pinfunction "2_2") (pintype "passive"))
      (node (ref "C26") (pin "2") (pinfunction "2_2") (pintype "passive"))
      (node (ref "C27") (pin "2") (pinfunction "2_2") (pintype "passive"))
      (node (ref "C28") (pin "2") (pinfunction "2_2") (pintype "passive"))
      (node (ref "C29") (pin "2") (pinfunction "2_2") (pintype "passive"))
      (node (ref "C3") (pin "-") (pinfunction "-_-") (pintype "passive"))
      (node (ref "C30") (pin "2") (pinfunction "2_2") (pintype "passive"))
      (node (ref "C31") (pin "2") (pinfunction "2_2") (pintype "passive"))
      (node (ref "C32") (pin "2") (pinfunction "2_2") (pintype "passive"))
      (node (ref "C33") (pin "2") (pinfunction "2_2") (pintype "passive"))
      (node (ref "C34") (pin "2") (pinfunction "2_2") (pintype "passive"))
      (node (ref "C35") (pin "1") (pinfunction "1_1") (pintype "passive"))
      (node (ref "C36") (pin "1") (pinfunction "1_1") (pintype "passive"))
      (node (ref "C37") (pin "2") (pinfunction "2_2") (pintype "passive"))
      (node (ref "C38") (pin "2") (pinfunction "2_2") (pintype "passive"))
      (node (ref "C39") (pin "1") (pinfunction "1_1") (pintype "passive"))
      (node (ref "C4") (pin "-") (pinfunction "-_-") (pintype "passive"))
      (node (ref "C40") (pin "1") (pinfunction "1_1") (pintype "passive"))
      (node (ref "C41") (pin "1") (pinfunction "1_1") (pintype "passive"))
      (node (ref "C42") (pin "1") (pinfunction "1_1") (pintype "passive"))
      (node (ref "C43") (pin "1") (pinfunction "1_1") (pintype "passive"))
      (node (ref "C44") (pin "1") (pinfunction "1_1") (pintype "passive"))
      (node (ref "C45") (pin "1") (pinfunction "1_1") (pintype "passive"))
      (node (ref "C46") (pin "1") (pinfunction "1_1") (pintype "passive"))
      (node (ref "C47") (pin "1") (pinfunction "1_1") (pintype "passive"))
      (node (ref "C48") (pin "1") (pinfunction "1_1") (pintype "passive"))
      (node (ref "C49") (pin "1") (pinfunction "1_1") (pintype "passive"))
      (node (ref "C5") (pin "2") (pinfunction "2_2") (pintype "passive"))
      (node (ref "C50") (pin "1") (pinfunction "1_1") (pintype "passive"))
      (node (ref "C51") (pin "1") (pinfunction "1_1") (pintype "passive"))
      (node (ref "C53") (pin "1") (pinfunction "1_1") (pintype "passive"))
      (node (ref "C54") (pin "2") (pinfunction "2_2") (pintype "passive"))
      (node (ref "C55") (pin "2") (pinfunction "2_2") (pintype "passive"))
      (node (ref "C56") (pin "2") (pinfunction "2_2") (pintype "passive"))
      (node (ref "C57") (pin "2") (pinfunction "2_2") (pintype "passive"))
      (node (ref "C58") (pin "2") (pinfunction "2_2") (pintype "passive"))
      (node (ref "C59") (pin "2") (pinfunction "2_2") (pintype "passive"))
      (node (ref "C6") (pin "2") (pinfunction "2_2") (pintype "passive"))
      (node (ref "C60") (pin "2") (pinfunction "2_2") (pintype "passive"))
      (node (ref "C61") (pin "2") (pinfunction "2_2") (pintype "passive"))
      (node (ref "C62") (pin "2") (pinfunction "2_2") (pintype "passive"))
      (node (ref "C63") (pin "2") (pinfunction "2_2") (pintype "passive"))
      (node (ref "C64") (pin "2") (pinfunction "2_2") (pintype "passive"))
      (node (ref "C65") (pin "2") (pinfunction "2_2") (pintype "passive"))
      (node (ref "C66") (pin "2") (pinfunction "2_2") (pintype "passive"))
      (node (ref "C67") (pin "2") (pinfunction "2_2") (pintype "passive"))
      (node (ref "C68") (pin "2") (pinfunction "2_2") (pintype "passive"))
      (node (ref "C69") (pin "2") (pinfunction "2_2") (pintype "passive"))
      (node (ref "C7") (pin "2") (pinfunction "2_2") (pintype "passive"))
      (node (ref "C70") (pin "2") (pinfunction "2_2") (pintype "passive"))
      (node (ref "C71") (pin "2") (pinfunction "2_2") (pintype "passive"))
      (node (ref "C72") (pin "2") (pinfunction "2_2") (pintype "passive"))
      (node (ref "C73") (pin "2") (pinfunction "2_2") (pintype "passive"))
      (node (ref "C74") (pin "2") (pinfunction "2_2") (pintype "passive"))
      (node (ref "C75") (pin "2") (pinfunction "2_2") (pintype "passive"))
      (node (ref "C76") (pin "2") (pinfunction "2_2") (pintype "passive"))
      (node (ref "C77") (pin "1") (pinfunction "1_1") (pintype "passive"))
      (node (ref "C78") (pin "2") (pinfunction "2_2") (pintype "passive"))
      (node (ref "C79") (pin "2") (pinfunction "2_2") (pintype "passive"))
      (node (ref "C8") (pin "2") (pinfunction "2_2") (pintype "passive"))
      (node (ref "C80") (pin "2") (pinfunction "2_2") (pintype "passive"))
      (node (ref "C81") (pin "2") (pinfunction "2_2") (pintype "passive"))
      (node (ref "C82") (pin "2") (pinfunction "2_2") (pintype "passive"))
      (node (ref "C83") (pin "2") (pinfunction "2_2") (pintype "passive"))
      (node (ref "C84") (pin "2") (pinfunction "2_2") (pintype "passive"))
      (node (ref "C85") (pin "2") (pinfunction "2_2") (pintype "passive"))
      (node (ref "C86") (pin "2") (pinfunction "2_2") (pintype "passive"))
      (node (ref "C87") (pin "2") (pinfunction "2_2") (pintype "passive"))
      (node (ref "C88") (pin "2") (pinfunction "2_2") (pintype "passive"))
      (node (ref "C89") (pin "2") (pinfunction "2_2") (pintype "passive"))
      (node (ref "C9") (pin "2") (pinfunction "2_2") (pintype "passive"))
      (node (ref "C90") (pin "2") (pinfunction "2_2") (pintype "passive"))
      (node (ref "C91") (pin "2") (pinfunction "2_2") (pintype "passive"))
      (node (ref "C92") (pin "2") (pinfunction "2_2") (pintype "passive"))
      (node (ref "C93") (pin "2") (pinfunction "2_2") (pintype "passive"))
      (node (ref "C94") (pin "2") (pinfunction "2_2") (pintype "passive"))
      (node (ref "C95") (pin "2") (pinfunction "2_2") (pintype "passive"))
      (node (ref "C96") (pin "2") (pinfunction "2_2") (pintype "passive"))
      (node (ref "C97") (pin "2") (pinfunction "2_2") (pintype "passive"))
      (node (ref "C99") (pin "2") (pinfunction "2_2") (pintype "passive"))
      (node (ref "J1") (pin "1") (pinfunction "1_1") (pintype "passive"))
      (node (ref "J1") (pin "2") (pinfunction "2_2") (pintype "passive"))
      (node (ref "JP1") (pin "5") (pinfunction "5_5") (pintype "passive"))
      (node (ref "LED2") (pin "C") (pinfunction "C_C") (pintype "passive"))
      (node (ref "LED3") (pin "C") (pinfunction "C_C") (pintype "passive"))
      (node (ref "R1") (pin "2") (pinfunction "2_2") (pintype "passive"))
      (node (ref "R12") (pin "1") (pinfunction "1_1") (pintype "passive"))
      (node (ref "R15") (pin "1") (pinfunction "1_1") (pintype "passive"))
      (node (ref "R16") (pin "1") (pinfunction "1_1") (pintype "passive"))
      (node (ref "R24") (pin "1") (pinfunction "1_1") (pintype "passive"))
      (node (ref "R25") (pin "1") (pinfunction "1_1") (pintype "passive"))
      (node (ref "R26") (pin "1") (pinfunction "1_1") (pintype "passive"))
      (node (ref "R27") (pin "1") (pinfunction "1_1") (pintype "passive"))
      (node (ref "R36") (pin "1") (pinfunction "1_1") (pintype "passive"))
      (node (ref "R38") (pin "1") (pinfunction "1_1") (pintype "passive"))
      (node (ref "R4") (pin "1") (pinfunction "1_1") (pintype "passive"))
      (node (ref "R42") (pin "1") (pinfunction "1_1") (pintype "passive"))
      (node (ref "R43") (pin "1") (pinfunction "1_1") (pintype "passive"))
      (node (ref "R5") (pin "1") (pinfunction "1_1") (pintype "passive"))
      (node (ref "R50") (pin "2") (pinfunction "2_2") (pintype "passive"))
      (node (ref "R51") (pin "2") (pinfunction "2_2") (pintype "passive"))
      (node (ref "R6") (pin "1") (pinfunction "1_1") (pintype "passive"))
      (node (ref "R7") (pin "1") (pinfunction "1_1") (pintype "passive"))
      (node (ref "RJ1") (pin "GND") (pinfunction "GND_GND") (pintype "bidirectional"))
      (node (ref "RJ1") (pin "SHIELD0") (pinfunction "SHIELD0_SHIELD0") (pintype "bidirectional"))
      (node (ref "RJ1") (pin "SHIELD1") (pinfunction "SHIELD1_SHIELD1") (pintype "bidirectional"))
      (node (ref "RJ2") (pin "GND") (pinfunction "GND_GND") (pintype "bidirectional"))
      (node (ref "RJ2") (pin "SHIELD0") (pinfunction "SHIELD0_SHIELD0") (pintype "bidirectional"))
      (node (ref "RJ2") (pin "SHIELD1") (pinfunction "SHIELD1_SHIELD1") (pintype "bidirectional"))
      (node (ref "SD/MMC1") (pin "6") (pinfunction "VSS_6") (pintype "power_in"))
      (node (ref "T1") (pin "2") (pinfunction "E_2") (pintype "passive"))
      (node (ref "T2") (pin "1") (pinfunction "B_1") (pintype "passive"))
      (node (ref "T2") (pin "2") (pinfunction "E_2") (pintype "passive"))
      (node (ref "U$1") (pin "4") (pinfunction "GND_4") (pintype "passive"))
      (node (ref "U1") (pin "105") (pinfunction "VSSA4_105") (pintype "power_in"))
      (node (ref "U1") (pin "112") (pinfunction "VSSA1_112") (pintype "power_in"))
      (node (ref "U1") (pin "118") (pinfunction "VSSA2_118") (pintype "power_in"))
      (node (ref "U1") (pin "30") (pinfunction "VSSD1_30") (pintype "power_in"))
      (node (ref "U1") (pin "35") (pinfunction "VSSD2_35") (pintype "power_in"))
      (node (ref "U1") (pin "98") (pinfunction "DCDC_GND_98") (pintype "power_in"))
      (node (ref "U2") (pin "12") (pinfunction "VSSQ2_12") (pintype "power_in"))
      (node (ref "U2") (pin "34") (pinfunction "VSS1_34") (pintype "power_in"))
      (node (ref "U2") (pin "48") (pinfunction "VSS2_48") (pintype "power_in"))
      (node (ref "U2") (pin "52") (pinfunction "VSSQ3_52") (pintype "power_in"))
      (node (ref "U2") (pin "58") (pinfunction "VSSQ4_58") (pintype "power_in"))
      (node (ref "U2") (pin "6") (pinfunction "VSSQ1_6") (pintype "power_in"))
      (node (ref "U2") (pin "64") (pinfunction "VSSQ5_64") (pintype "power_in"))
      (node (ref "U2") (pin "66") (pinfunction "VSS3_66") (pintype "power_in"))
      (node (ref "U3") (pin "13") (pinfunction "VSS_13") (pintype "power_in"))
      (node (ref "U3") (pin "36") (pinfunction "VSS_36") (pintype "power_in"))
      (node (ref "U4") (pin "34") (pinfunction "TEST2_34") (pintype "passive"))
      (node (ref "U4") (pin "44") (pinfunction "CLK24_EN_44") (pintype "passive"))
      (node (ref "U4") (pin "65") (pinfunction "EPAD_65") (pintype "passive"))
      (node (ref "U5") (pin "13") (pinfunction "TEST2_13") (pintype "power_in"))
      (node (ref "U5") (pin "33") (pinfunction "TEST3_33") (pintype "power_in"))
      (node (ref "U6") (pin "6") (pinfunction "GND_6") (pintype "power_in"))
      (node (ref "X1") (pin "4") (pinfunction "4_4") (pintype "passive"))
      (node (ref "X1") (pin "S1") (pinfunction "S1_S1") (pintype "passive"))
      (node (ref "X1") (pin "S2") (pinfunction "S2_S2") (pintype "passive"))
    )
    (net (code "122") (name "Net-(LED1-PadA)") (class "Default")
      (node (ref "LED1") (pin "A") (pinfunction "A_A") (pintype "passive"))
      (node (ref "R33") (pin "2") (pinfunction "2_2") (pintype "passive"))
    )
    (net (code "123") (name "Net-(LED2-PadA)") (class "Default")
      (node (ref "LED2") (pin "A") (pinfunction "A_A") (pintype "passive"))
      (node (ref "R40") (pin "1") (pinfunction "1_1") (pintype "passive"))
    )
    (net (code "124") (name "Net-(LED3-PadA)") (class "Default")
      (node (ref "LED3") (pin "A") (pinfunction "A_A") (pintype "passive"))
      (node (ref "R41") (pin "1") (pinfunction "1_1") (pintype "passive"))
    )
    (net (code "125") (name "Net-(LED4-PadA)") (class "Default")
      (node (ref "LED4") (pin "A") (pinfunction "A_A") (pintype "passive"))
      (node (ref "R49") (pin "2") (pinfunction "2_2") (pintype "passive"))
    )
    (net (code "126") (name "Net-(R5-Pad2)") (class "Default")
      (node (ref "R5") (pin "2") (pinfunction "2_2") (pintype "passive"))
      (node (ref "RJ1") (pin "G-") (pinfunction "G-_G-") (pintype "bidirectional"))
    )
    (net (code "127") (name "Net-(R6-Pad2)") (class "Default")
      (node (ref "R6") (pin "2") (pinfunction "2_2") (pintype "passive"))
      (node (ref "RJ1") (pin "Y-") (pinfunction "Y-_Y-") (pintype "bidirectional"))
    )
    (net (code "128") (name "Net-(R20-Pad1)") (class "Default")
      (node (ref "R20") (pin "1") (pinfunction "1_1") (pintype "passive"))
      (node (ref "SW1") (pin "1") (pinfunction "1_1") (pintype "passive"))
    )
    (net (code "129") (name "Net-(R21-Pad1)") (class "Default")
      (node (ref "R21") (pin "1") (pinfunction "1_1") (pintype "passive"))
      (node (ref "SW1") (pin "2") (pinfunction "2_2") (pintype "passive"))
    )
    (net (code "130") (name "Net-(R22-Pad1)") (class "Default")
      (node (ref "R22") (pin "1") (pinfunction "1_1") (pintype "passive"))
      (node (ref "SW1") (pin "3") (pinfunction "3_3") (pintype "passive"))
    )
    (net (code "131") (name "Net-(R23-Pad1)") (class "Default")
      (node (ref "R23") (pin "1") (pinfunction "1_1") (pintype "passive"))
      (node (ref "SW1") (pin "4") (pinfunction "4_4") (pintype "passive"))
    )
    (net (code "132") (name "Net-(R42-Pad2)") (class "Default")
      (node (ref "R42") (pin "2") (pinfunction "2_2") (pintype "passive"))
      (node (ref "RJ2") (pin "G-") (pinfunction "G-_G-") (pintype "bidirectional"))
    )
    (net (code "133") (name "Net-(R43-Pad2)") (class "Default")
      (node (ref "R43") (pin "2") (pinfunction "2_2") (pintype "passive"))
      (node (ref "RJ2") (pin "Y-") (pinfunction "Y-_Y-") (pintype "bidirectional"))
    )
    (net (code "134") (name "Net-(RJ1-RXCT)") (class "Default")
      (node (ref "C73") (pin "1") (pinfunction "1_1") (pintype "passive"))
      (node (ref "R28") (pin "2") (pinfunction "2_2") (pintype "passive"))
      (node (ref "RJ1") (pin "P4") (pinfunction "TXCT_P4") (pintype "bidirectional"))
      (node (ref "RJ1") (pin "P5") (pinfunction "RXCT_P5") (pintype "bidirectional"))
    )
    (net (code "135") (name "Net-(RJ2-RXCT)") (class "Default")
      (node (ref "C82") (pin "1") (pinfunction "1_1") (pintype "passive"))
      (node (ref "R44") (pin "2") (pinfunction "2_2") (pintype "passive"))
      (node (ref "RJ2") (pin "P4") (pinfunction "TXCT_P4") (pintype "bidirectional"))
      (node (ref "RJ2") (pin "P5") (pinfunction "RXCT_P5") (pintype "bidirectional"))
    )
    (net (code "136") (name "Net-(S1-S)") (class "Default")
      (node (ref "R1") (pin "1") (pinfunction "1_1") (pintype "passive"))
      (node (ref "R2") (pin "1") (pinfunction "1_1") (pintype "passive"))
      (node (ref "S1") (pin "1") (pinfunction "S_1") (pintype "passive"))
      (node (ref "S1") (pin "2") (pinfunction "S1_2") (pintype "passive"))
    )
    (net (code "137") (name "Net-(S2-S)") (class "Default")
      (node (ref "R3") (pin "1") (pinfunction "1_1") (pintype "passive"))
      (node (ref "S2") (pin "1") (pinfunction "S_1") (pintype "passive"))
      (node (ref "S2") (pin "2") (pinfunction "S1_2") (pintype "passive"))
    )
    (net (code "138") (name "Net-(SD/MMC1-VDD)") (class "Default")
      (node (ref "C40") (pin "2") (pinfunction "2_2") (pintype "passive"))
      (node (ref "C41") (pin "2") (pinfunction "2_2") (pintype "passive"))
      (node (ref "L3") (pin "2") (pinfunction "2_2") (pintype "passive"))
      (node (ref "SD/MMC1") (pin "4") (pinfunction "VDD_4") (pintype "power_in"))
    )
    (net (code "139") (name "Net-(T1-B)") (class "Default")
      (node (ref "C6") (pin "1") (pinfunction "1_1") (pintype "passive"))
      (node (ref "R3") (pin "2") (pinfunction "2_2") (pintype "passive"))
      (node (ref "R4") (pin "2") (pinfunction "2_2") (pintype "passive"))
      (node (ref "T1") (pin "1") (pinfunction "B_1") (pintype "passive"))
    )
    (net (code "140") (name "Net-(U$1-VI)") (class "Default")
      (node (ref "C1") (pin "1") (pinfunction "1_1") (pintype "passive"))
      (node (ref "J1") (pin "3") (pinfunction "3_3") (pintype "passive"))
      (node (ref "U$1") (pin "1") (pinfunction "VI_1") (pintype "input"))
    )
    (net (code "141") (name "Net-(U1-DCDC_LN1)") (class "Default")
      (node (ref "L2") (pin "2") (pinfunction "2_2") (pintype "passive"))
      (node (ref "U1") (pin "97") (pinfunction "DCDC_LN1_97") (pintype "passive"))
    )
    (net (code "142") (name "Net-(U1-DCDC_LP)") (class "Default")
      (node (ref "L2") (pin "1") (pinfunction "1_1") (pintype "passive"))
      (node (ref "U1") (pin "99") (pinfunction "DCDC_LP_99") (pintype "passive"))
    )
    (net (code "143") (name "Net-(U1-LCD_RS)") (class "Default")
      (node (ref "R19") (pin "1") (pinfunction "1_1") (pintype "passive"))
      (node (ref "U1") (pin "14") (pinfunction "LCD_RS_14") (pintype "bidirectional"))
    )
    (net (code "144") (name "Net-(U1-VAG)") (class "Default")
      (node (ref "C39") (pin "2") (pinfunction "2_2") (pintype "passive"))
      (node (ref "U1") (pin "117") (pinfunction "VAG_117") (pintype "passive"))
    )
    (net (code "145") (name "Net-(U2-VREF)") (class "Default")
      (node (ref "C52") (pin "1") (pinfunction "1_1") (pintype "passive"))
      (node (ref "C53") (pin "2") (pinfunction "2_2") (pintype "passive"))
      (node (ref "R16") (pin "2") (pinfunction "2_2") (pintype "passive"))
      (node (ref "R17") (pin "1") (pinfunction "1_1") (pintype "passive"))
      (node (ref "U2") (pin "49") (pinfunction "VREF_49") (pintype "input"))
    )
    (net (code "146") (name "Net-(U4-AUTOMDIX_EN)") (class "Default")
      (node (ref "R39") (pin "2") (pinfunction "2_2") (pintype "passive"))
      (node (ref "U4") (pin "41") (pinfunction "AUTOMDIX_EN_41") (pintype "passive"))
    )
    (net (code "147") (name "Net-(U4-EXRES)") (class "Default")
      (node (ref "R38") (pin "2") (pinfunction "2_2") (pintype "passive"))
      (node (ref "U4") (pin "50") (pinfunction "EXRES_50") (pintype "passive"))
    )
    (net (code "148") (name "Net-(U4-NRESET)") (class "Default")
      (node (ref "C76") (pin "1") (pinfunction "1_1") (pintype "passive"))
      (node (ref "R37") (pin "1") (pinfunction "1_1") (pintype "passive"))
      (node (ref "U4") (pin "12") (pinfunction "NRESET_12") (pintype "passive"))
    )
    (net (code "149") (name "Net-(U4-USBRBIAS)") (class "Default")
      (node (ref "R36") (pin "2") (pinfunction "2_2") (pintype "passive"))
      (node (ref "U4") (pin "63") (pinfunction "USBRBIAS_63") (pintype "passive"))
    )
    (net (code "150") (name "Net-(U4-VBUS_DET)") (class "Default")
      (node (ref "R35") (pin "1") (pinfunction "1_1") (pintype "passive"))
      (node (ref "U4") (pin "11") (pinfunction "VBUS_DET_11") (pintype "power_in"))
    )
    (net (code "151") (name "Net-(U4-XI)") (class "Default")
      (node (ref "C75") (pin "1") (pinfunction "1_1") (pintype "passive"))
      (node (ref "HC49US") (pin "2") (pinfunction "2_2") (pintype "passive"))
      (node (ref "R34") (pin "2") (pinfunction "2_2") (pintype "passive"))
      (node (ref "U4") (pin "61") (pinfunction "XI_61") (pintype "passive"))
    )
    (net (code "152") (name "Net-(U4-XO)") (class "Default")
      (node (ref "C74") (pin "1") (pinfunction "1_1") (pintype "passive"))
      (node (ref "HC49US") (pin "1") (pinfunction "1_1") (pintype "passive"))
      (node (ref "R34") (pin "1") (pinfunction "1_1") (pintype "passive"))
      (node (ref "U4") (pin "60") (pinfunction "XO_60") (pintype "passive"))
    )
    (net (code "153") (name "Net-(U5A-EXRES)") (class "Default")
      (node (ref "R50") (pin "1") (pinfunction "1_1") (pintype "passive"))
      (node (ref "U5") (pin "8") (pinfunction "EXRES_8") (pintype "input"))
    )
    (net (code "154") (name "Net-(U5A-USBRBIAS)") (class "Default")
      (node (ref "R51") (pin "1") (pinfunction "1_1") (pintype "passive"))
      (node (ref "U5") (pin "16") (pinfunction "USBRBIAS_16") (pintype "input"))
    )
    (net (code "155") (name "Net-(U5A-VBUS_DET)") (class "Default")
      (node (ref "R52") (pin "1") (pinfunction "1_1") (pintype "passive"))
      (node (ref "U5") (pin "20") (pinfunction "VBUS_DET_20") (pintype "power_in"))
    )
    (net (code "156") (name "Net-(U5A-VDDUSBPLL)") (class "Default")
      (node (ref "L5") (pin "2") (pinfunction "2_2") (pintype "passive"))
      (node (ref "U5") (pin "17") (pinfunction "VDDUSBPLL_17") (pintype "power_in"))
    )
    (net (code "157") (name "Net-(U5A-XO)") (class "Default")
      (node (ref "C85") (pin "1") (pinfunction "1_1") (pintype "passive"))
      (node (ref "HC49US1") (pin "2") (pinfunction "2_2") (pintype "passive"))
      (node (ref "U5") (pin "19") (pinfunction "XO_19") (pintype "output"))
    )
    (net (code "158") (name "unconnected-(RJ1-PadNC)") (class "Default")
      (node (ref "RJ1") (pin "NC") (pinfunction "NC_NC") (pintype "bidirectional"))
    )
    (net (code "159") (name "unconnected-(RJ2-PadNC)") (class "Default")
      (node (ref "RJ2") (pin "NC") (pinfunction "NC_NC") (pintype "bidirectional"))
    )
    (net (code "160") (name "unconnected-(SD/MMC1-CP_E-Pad9)") (class "Default")
      (node (ref "SD/MMC1") (pin "9") (pinfunction "CP_E_9") (pintype "input"))
    )
    (net (code "161") (name "unconnected-(SD/MMC1-PACK1-Pad10)") (class "Default")
      (node (ref "SD/MMC1") (pin "10") (pinfunction "PACK1_10") (pintype "input"))
    )
    (net (code "162") (name "unconnected-(U1-GPMI_CE1N-Pad81)") (class "Default")
      (node (ref "U1") (pin "81") (pinfunction "GPMI_CE1N_81") (pintype "bidirectional"))
    )
    (net (code "163") (name "unconnected-(U1-GPMI_RDY1{slash}SSP2_CMD-Pad21)") (class "Default")
      (node (ref "U1") (pin "21") (pinfunction "GPMI_RDY1/SSP2_CMD_21") (pintype "bidirectional"))
    )
    (net (code "164") (name "unconnected-(U1-HPL-Pad113)") (class "Default")
      (node (ref "U1") (pin "113") (pinfunction "HPL_113") (pintype "output"))
    )
    (net (code "165") (name "unconnected-(U1-HPR-Pad109)") (class "Default")
      (node (ref "U1") (pin "109") (pinfunction "HPR_109") (pintype "output"))
    )
    (net (code "166") (name "unconnected-(U1-LCD_CS-Pad10)") (class "Default")
      (node (ref "U1") (pin "10") (pinfunction "LCD_CS_10") (pintype "bidirectional"))
    )
    (net (code "167") (name "unconnected-(U1-LCD_D04-Pad6)") (class "Default")
      (node (ref "U1") (pin "6") (pinfunction "LCD_D04_6") (pintype "bidirectional"))
    )
    (net (code "168") (name "unconnected-(U1-LCD_D05-Pad7)") (class "Default")
      (node (ref "U1") (pin "7") (pinfunction "LCD_D05_7") (pintype "bidirectional"))
    )
    (net (code "169") (name "unconnected-(U1-LCD_D06-Pad8)") (class "Default")
      (node (ref "U1") (pin "8") (pinfunction "LCD_D06_8") (pintype "bidirectional"))
    )
    (net (code "170") (name "unconnected-(U1-LCD_D07-Pad9)") (class "Default")
      (node (ref "U1") (pin "9") (pinfunction "LCD_D07_9") (pintype "bidirectional"))
    )
    (net (code "171") (name "unconnected-(U1-LCD_DOTCK{slash}GPMI_RDY3-Pad17)") (class "Default")
      (node (ref "U1") (pin "17") (pinfunction "LCD_DOTCK/GPMI_RDY3_17") (pintype "bidirectional"))
    )
    (net (code "172") (name "unconnected-(U1-LCD_RESET{slash}GPMI_CE3N-Pad12)") (class "Default")
      (node (ref "U1") (pin "12") (pinfunction "LCD_RESET/GPMI_CE3N_12") (pintype "bidirectional"))
    )
    (net (code "173") (name "unconnected-(U1-LCD_VSYNC{slash}LCD_BUSY-Pad16)") (class "Default")
      (node (ref "U1") (pin "16") (pinfunction "LCD_VSYNC/LCD_BUSY_16") (pintype "bidirectional"))
    )
    (net (code "174") (name "unconnected-(U1-LCD_WR-Pad13)") (class "Default")
      (node (ref "U1") (pin "13") (pinfunction "LCD_WR_13") (pintype "bidirectional"))
    )
    (net (code "175") (name "unconnected-(U1-LINE1_INL-Pad115)") (class "Default")
      (node (ref "U1") (pin "115") (pinfunction "LINE1_INL_115") (pintype "input"))
    )
    (net (code "176") (name "unconnected-(U1-LINE1_INR-Pad114)") (class "Default")
      (node (ref "U1") (pin "114") (pinfunction "LINE1_INR_114") (pintype "input"))
    )
    (net (code "177") (name "unconnected-(U1-LRADC0-Pad108)") (class "Default")
      (node (ref "U1") (pin "108") (pinfunction "LRADC0_108") (pintype "bidirectional"))
    )
    (net (code "178") (name "unconnected-(U1-LRADC1-Pad107)") (class "Default")
      (node (ref "U1") (pin "107") (pinfunction "LRADC1_107") (pintype "bidirectional"))
    )
    (net (code "179") (name "unconnected-(U1-MIC-Pad116)") (class "Default")
      (node (ref "U1") (pin "116") (pinfunction "MIC_116") (pintype "input"))
    )
    (net (code "180") (name "unconnected-(U1-PWM2{slash}GPMI_RDY3-Pad91)") (class "Default")
      (node (ref "U1") (pin "91") (pinfunction "PWM2/GPMI_RDY3_91") (pintype "bidirectional"))
    )
    (net (code "181") (name "unconnected-(U1-SSP1_DETECT{slash}GPMI_CE3N{slash}USB_ID-Pad88)") (class "Default")
      (node (ref "U1") (pin "88") (pinfunction "SSP1_DETECT/GPMI_CE3N/USB_ID_88") (pintype "bidirectional"))
    )
    (net (code "182") (name "unconnected-(U1-VDAC1-Pad104)") (class "Default")
      (node (ref "U1") (pin "104") (pinfunction "VDAC1_104") (pintype "output"))
    )
    (net (code "183") (name "unconnected-(U2-NC1-Pad14)") (class "Default")
      (node (ref "U2") (pin "14") (pinfunction "NC1_14") (pintype "no_connect"))
    )
    (net (code "184") (name "unconnected-(U2-NC2-Pad17)") (class "Default")
      (node (ref "U2") (pin "17") (pinfunction "NC2_17") (pintype "no_connect"))
    )
    (net (code "185") (name "unconnected-(U2-NC3-Pad19)") (class "Default")
      (node (ref "U2") (pin "19") (pinfunction "NC3_19") (pintype "no_connect"))
    )
    (net (code "186") (name "unconnected-(U2-NC4-Pad25)") (class "Default")
      (node (ref "U2") (pin "25") (pinfunction "NC4_25") (pintype "no_connect"))
    )
    (net (code "187") (name "unconnected-(U2-NC5-Pad43)") (class "Default")
      (node (ref "U2") (pin "43") (pinfunction "NC5_43") (pintype "no_connect"))
    )
    (net (code "188") (name "unconnected-(U2-NC6-Pad50)") (class "Default")
      (node (ref "U2") (pin "50") (pinfunction "NC6_50") (pintype "no_connect"))
    )
    (net (code "189") (name "unconnected-(U2-NC7-Pad53)") (class "Default")
      (node (ref "U2") (pin "53") (pinfunction "NC7_53") (pintype "no_connect"))
    )
    (net (code "190") (name "unconnected-(U3-NC-Pad1)") (class "Default")
      (node (ref "U3") (pin "1") (pinfunction "NC_1") (pintype "no_connect"))
    )
    (net (code "191") (name "unconnected-(U3-NC-Pad2)") (class "Default")
      (node (ref "U3") (pin "2") (pinfunction "NC_2") (pintype "no_connect"))
    )
    (net (code "192") (name "unconnected-(U3-NC-Pad3)") (class "Default")
      (node (ref "U3") (pin "3") (pinfunction "NC_3") (pintype "no_connect"))
    )
    (net (code "193") (name "unconnected-(U3-NC-Pad4)") (class "Default")
      (node (ref "U3") (pin "4") (pinfunction "NC_4") (pintype "no_connect"))
    )
    (net (code "194") (name "unconnected-(U3-NC-Pad5)") (class "Default")
      (node (ref "U3") (pin "5") (pinfunction "NC_5") (pintype "no_connect"))
    )
    (net (code "195") (name "unconnected-(U3-NC-Pad6)") (class "Default")
      (node (ref "U3") (pin "6") (pinfunction "NC_6") (pintype "no_connect"))
    )
    (net (code "196") (name "unconnected-(U3-NC-Pad10)") (class "Default")
      (node (ref "U3") (pin "10") (pinfunction "NC_10") (pintype "no_connect"))
    )
    (net (code "197") (name "unconnected-(U3-NC-Pad11)") (class "Default")
      (node (ref "U3") (pin "11") (pinfunction "NC_11") (pintype "no_connect"))
    )
    (net (code "198") (name "unconnected-(U3-NC-Pad14)") (class "Default")
      (node (ref "U3") (pin "14") (pinfunction "NC_14") (pintype "no_connect"))
    )
    (net (code "199") (name "unconnected-(U3-NC-Pad15)") (class "Default")
      (node (ref "U3") (pin "15") (pinfunction "NC_15") (pintype "no_connect"))
    )
    (net (code "200") (name "unconnected-(U3-NC-Pad20)") (class "Default")
      (node (ref "U3") (pin "20") (pinfunction "NC_20") (pintype "no_connect"))
    )
    (net (code "201") (name "unconnected-(U3-NC-Pad21)") (class "Default")
      (node (ref "U3") (pin "21") (pinfunction "NC_21") (pintype "no_connect"))
    )
    (net (code "202") (name "unconnected-(U3-NC-Pad22)") (class "Default")
      (node (ref "U3") (pin "22") (pinfunction "NC_22") (pintype "no_connect"))
    )
    (net (code "203") (name "unconnected-(U3-NC-Pad23)") (class "Default")
      (node (ref "U3") (pin "23") (pinfunction "NC_23") (pintype "no_connect"))
    )
    (net (code "204") (name "unconnected-(U3-NC-Pad24)") (class "Default")
      (node (ref "U3") (pin "24") (pinfunction "NC_24") (pintype "no_connect"))
    )
    (net (code "205") (name "unconnected-(U3-NC-Pad25)") (class "Default")
      (node (ref "U3") (pin "25") (pinfunction "NC_25") (pintype "no_connect"))
    )
    (net (code "206") (name "unconnected-(U3-NC-Pad26)") (class "Default")
      (node (ref "U3") (pin "26") (pinfunction "NC_26") (pintype "no_connect"))
    )
    (net (code "207") (name "unconnected-(U3-NC-Pad27)") (class "Default")
      (node (ref "U3") (pin "27") (pinfunction "NC_27") (pintype "no_connect"))
    )
    (net (code "208") (name "unconnected-(U3-NC-Pad28)") (class "Default")
      (node (ref "U3") (pin "28") (pinfunction "NC_28") (pintype "no_connect"))
    )
    (net (code "209") (name "unconnected-(U3-NC-Pad33)") (class "Default")
      (node (ref "U3") (pin "33") (pinfunction "NC_33") (pintype "no_connect"))
    )
    (net (code "210") (name "unconnected-(U3-NC-Pad34)") (class "Default")
      (node (ref "U3") (pin "34") (pinfunction "NC_34") (pintype "no_connect"))
    )
    (net (code "211") (name "unconnected-(U3-NC-Pad35)") (class "Default")
      (node (ref "U3") (pin "35") (pinfunction "NC_35") (pintype "no_connect"))
    )
    (net (code "212") (name "unconnected-(U3-NC-Pad38)") (class "Default")
      (node (ref "U3") (pin "38") (pinfunction "NC_38") (pintype "no_connect"))
    )
    (net (code "213") (name "unconnected-(U3-NC-Pad39)") (class "Default")
      (node (ref "U3") (pin "39") (pinfunction "NC_39") (pintype "no_connect"))
    )
    (net (code "214") (name "unconnected-(U3-NC-Pad40)") (class "Default")
      (node (ref "U3") (pin "40") (pinfunction "NC_40") (pintype "no_connect"))
    )
    (net (code "215") (name "unconnected-(U3-NC-Pad45)") (class "Default")
      (node (ref "U3") (pin "45") (pinfunction "NC_45") (pintype "no_connect"))
    )
    (net (code "216") (name "unconnected-(U3-NC-Pad46)") (class "Default")
      (node (ref "U3") (pin "46") (pinfunction "NC_46") (pintype "no_connect"))
    )
    (net (code "217") (name "unconnected-(U3-NC-Pad47)") (class "Default")
      (node (ref "U3") (pin "47") (pinfunction "NC_47") (pintype "no_connect"))
    )
    (net (code "218") (name "unconnected-(U3-NC-Pad48)") (class "Default")
      (node (ref "U3") (pin "48") (pinfunction "NC_48") (pintype "no_connect"))
    )
    (net (code "219") (name "unconnected-(U4-CLK24_OUT-Pad45)") (class "Default")
      (node (ref "U4") (pin "45") (pinfunction "CLK24_OUT_45") (pintype "passive"))
    )
    (net (code "220") (name "unconnected-(U4-EECLK-Pad23)") (class "Default")
      (node (ref "U4") (pin "23") (pinfunction "EECLK_23") (pintype "passive"))
    )
    (net (code "221") (name "unconnected-(U4-EECS-Pad24)") (class "Default")
      (node (ref "U4") (pin "24") (pinfunction "EECS_24") (pintype "passive"))
    )
    (net (code "222") (name "unconnected-(U4-EEDI-Pad26)") (class "Default")
      (node (ref "U4") (pin "26") (pinfunction "EEDI_26") (pintype "passive"))
    )
    (net (code "223") (name "unconnected-(U4-EEDO-Pad25)") (class "Default")
      (node (ref "U4") (pin "25") (pinfunction "EEDO_25") (pintype "passive"))
    )
    (net (code "224") (name "unconnected-(U4-GPIO3-Pad35)") (class "Default")
      (node (ref "U4") (pin "35") (pinfunction "GPIO3_35") (pintype "bidirectional"))
    )
    (net (code "225") (name "unconnected-(U4-GPIO4-Pad36)") (class "Default")
      (node (ref "U4") (pin "36") (pinfunction "GPIO4_36") (pintype "bidirectional"))
    )
    (net (code "226") (name "unconnected-(U4-GPIO5-Pad37)") (class "Default")
      (node (ref "U4") (pin "37") (pinfunction "GPIO5_37") (pintype "bidirectional"))
    )
    (net (code "227") (name "unconnected-(U4-GPIO6-Pad42)") (class "Default")
      (node (ref "U4") (pin "42") (pinfunction "GPIO6_42") (pintype "bidirectional"))
    )
    (net (code "228") (name "unconnected-(U4-GPIO7-Pad43)") (class "Default")
      (node (ref "U4") (pin "43") (pinfunction "GPIO7_43") (pintype "bidirectional"))
    )
    (net (code "229") (name "unconnected-(U4-NC-Pad18)") (class "Default")
      (node (ref "U4") (pin "18") (pinfunction "NC_18") (pintype "no_connect"))
    )
    (net (code "230") (name "unconnected-(U4-NC_2-Pad6)") (class "Default")
      (node (ref "U4") (pin "6") (pinfunction "NC_2_6") (pintype "no_connect"))
    )
    (net (code "231") (name "unconnected-(U4-NC_3-Pad7)") (class "Default")
      (node (ref "U4") (pin "7") (pinfunction "NC_3_7") (pintype "no_connect"))
    )
    (net (code "232") (name "unconnected-(U4-NC_4-Pad8)") (class "Default")
      (node (ref "U4") (pin "8") (pinfunction "NC_4_8") (pintype "no_connect"))
    )
    (net (code "233") (name "unconnected-(U4-NC_5-Pad9)") (class "Default")
      (node (ref "U4") (pin "9") (pinfunction "NC_5_9") (pintype "no_connect"))
    )
    (net (code "234") (name "unconnected-(U4-NC_6-Pad17)") (class "Default")
      (node (ref "U4") (pin "17") (pinfunction "NC_6_17") (pintype "no_connect"))
    )
    (net (code "235") (name "unconnected-(U4-TDO-Pad31)") (class "Default")
      (node (ref "U4") (pin "31") (pinfunction "TDO_31") (pintype "passive"))
    )
    (net (code "236") (name "unconnected-(U4-TEST1-Pad13)") (class "Default")
      (node (ref "U4") (pin "13") (pinfunction "TEST1_13") (pintype "passive"))
    )
    (net (code "237") (name "unconnected-(U4-TEST4-Pad47)") (class "Default")
      (node (ref "U4") (pin "47") (pinfunction "TEST4_47") (pintype "passive"))
    )
    (net (code "238") (name "unconnected-(U5A-EEDI-Pad32)") (class "Default")
      (node (ref "U5") (pin "32") (pinfunction "EEDI_32") (pintype "input"))
    )
    (net (code "239") (name "unconnected-(U5A-EEDO{slash}~{AUTOMDIX_EN}-Pad31)") (class "Default")
      (node (ref "U5") (pin "31") (pinfunction "EEDO/~{AUTOMDIX_EN}_31") (pintype "passive"))
    )
    (net (code "240") (name "unconnected-(U5A-EP-Pad57)") (class "Default")
      (node (ref "U5") (pin "57") (pinfunction "EP_57") (pintype "passive"))
    )
    (net (code "241") (name "unconnected-(U5A-MDC{slash}GPIO2-Pad22)") (class "Default")
      (node (ref "U5") (pin "22") (pinfunction "MDC/GPIO2_22") (pintype "bidirectional"))
    )
    (net (code "242") (name "unconnected-(U5A-MDIO{slash}GPIO1-Pad23)") (class "Default")
      (node (ref "U5") (pin "23") (pinfunction "MDIO/GPIO1_23") (pintype "bidirectional"))
    )
    (net (code "243") (name "unconnected-(U5A-NC-Pad14)") (class "Default")
      (node (ref "U5") (pin "14") (pinfunction "NC_14") (pintype "no_connect"))
    )
    (net (code "244") (name "unconnected-(U5A-NC_2-Pad7)") (class "Default")
      (node (ref "U5") (pin "7") (pinfunction "NC_2_7") (pintype "no_connect"))
    )
    (net (code "245") (name "unconnected-(U5A-NPHY_INT-Pad1)") (class "Default")
      (node (ref "U5") (pin "1") (pinfunction "NPHY_INT_1") (pintype "passive"))
    )
    (net (code "246") (name "unconnected-(U5A-RXCLK-Pad41)") (class "Default")
      (node (ref "U5") (pin "41") (pinfunction "RXCLK_41") (pintype "input"))
    )
    (net (code "247") (name "unconnected-(U5B-COL{slash}GPIO0-Pad46)") (class "Default")
      (node (ref "U5") (pin "46") (pinfunction "COL/GPIO0_46") (pintype "bidirectional"))
    )
    (net (code "248") (name "unconnected-(U5B-CRS{slash}GPIO3-Pad45)") (class "Default")
      (node (ref "U5") (pin "45") (pinfunction "CRS/GPIO3_45") (pintype "bidirectional"))
    )
    (net (code "249") (name "unconnected-(U5B-EECLK{slash}~{PWR_SEL}-Pad29)") (class "Default")
      (node (ref "U5") (pin "29") (pinfunction "EECLK/~{PWR_SEL}_29") (pintype "input"))
    )
    (net (code "250") (name "unconnected-(U5B-EECS-Pad30)") (class "Default")
      (node (ref "U5") (pin "30") (pinfunction "EECS_30") (pintype "input"))
    )
    (net (code "251") (name "unconnected-(U5B-NTRST{slash}RXD0-Pad36)") (class "Default")
      (node (ref "U5") (pin "36") (pinfunction "NTRST/RXD0_36") (pintype "input"))
    )
    (net (code "252") (name "unconnected-(U5B-PHY_SEL-Pad34)") (class "Default")
      (node (ref "U5") (pin "34") (pinfunction "PHY_SEL_34") (pintype "input"))
    )
    (net (code "253") (name "unconnected-(U5B-RXDV-Pad42)") (class "Default")
      (node (ref "U5") (pin "42") (pinfunction "RXDV_42") (pintype "input"))
    )
    (net (code "254") (name "unconnected-(U5B-RXER-Pad44)") (class "Default")
      (node (ref "U5") (pin "44") (pinfunction "RXER_44") (pintype "input"))
    )
    (net (code "255") (name "unconnected-(U5B-TCK{slash}RXD1-Pad38)") (class "Default")
      (node (ref "U5") (pin "38") (pinfunction "TCK/RXD1_38") (pintype "input"))
    )
    (net (code "256") (name "unconnected-(U5B-TDI{slash}RXD3-Pad40)") (class "Default")
      (node (ref "U5") (pin "40") (pinfunction "TDI/RXD3_40") (pintype "input"))
    )
    (net (code "257") (name "unconnected-(U5B-TDO{slash}NPHY_RST-Pad37)") (class "Default")
      (node (ref "U5") (pin "37") (pinfunction "TDO/NPHY_RST_37") (pintype "output"))
    )
    (net (code "258") (name "unconnected-(U5B-TMS{slash}RXD2-Pad39)") (class "Default")
      (node (ref "U5") (pin "39") (pinfunction "TMS/RXD2_39") (pintype "input"))
    )
    (net (code "259") (name "unconnected-(U5B-TXCLK-Pad47)") (class "Default")
      (node (ref "U5") (pin "47") (pinfunction "TXCLK_47") (pintype "input"))
    )
    (net (code "260") (name "unconnected-(U5B-TXD0{slash}GPIO4{slash}~{EEP_DISABLE}-Pad56)") (class "Default")
      (node (ref "U5") (pin "56") (pinfunction "TXD0/GPIO4/~{EEP_DISABLE}_56") (pintype "bidirectional"))
    )
    (net (code "261") (name "unconnected-(U5B-TXD1{slash}GPIO5{slash}~{RMT_WKP}-Pad55)") (class "Default")
      (node (ref "U5") (pin "55") (pinfunction "TXD1/GPIO5/~{RMT_WKP}_55") (pintype "bidirectional"))
    )
    (net (code "262") (name "unconnected-(U5B-TXD2{slash}GPIO6{slash}~{PORT_SWAP}-Pad54)") (class "Default")
      (node (ref "U5") (pin "54") (pinfunction "TXD2/GPIO6/~{PORT_SWAP}_54") (pintype "bidirectional"))
    )
    (net (code "263") (name "unconnected-(U5B-TXD3{slash}GPIO7{slash}~{EEP_SIZE}-Pad53)") (class "Default")
      (node (ref "U5") (pin "53") (pinfunction "TXD3/GPIO7/~{EEP_SIZE}_53") (pintype "bidirectional"))
    )
    (net (code "264") (name "unconnected-(U5B-TXEN-Pad43)") (class "Default")
      (node (ref "U5") (pin "43") (pinfunction "TXEN_43") (pintype "output"))
    )
  )
)
